# rs41.net
KiCad netlist of a schematic drawn in EAGLE
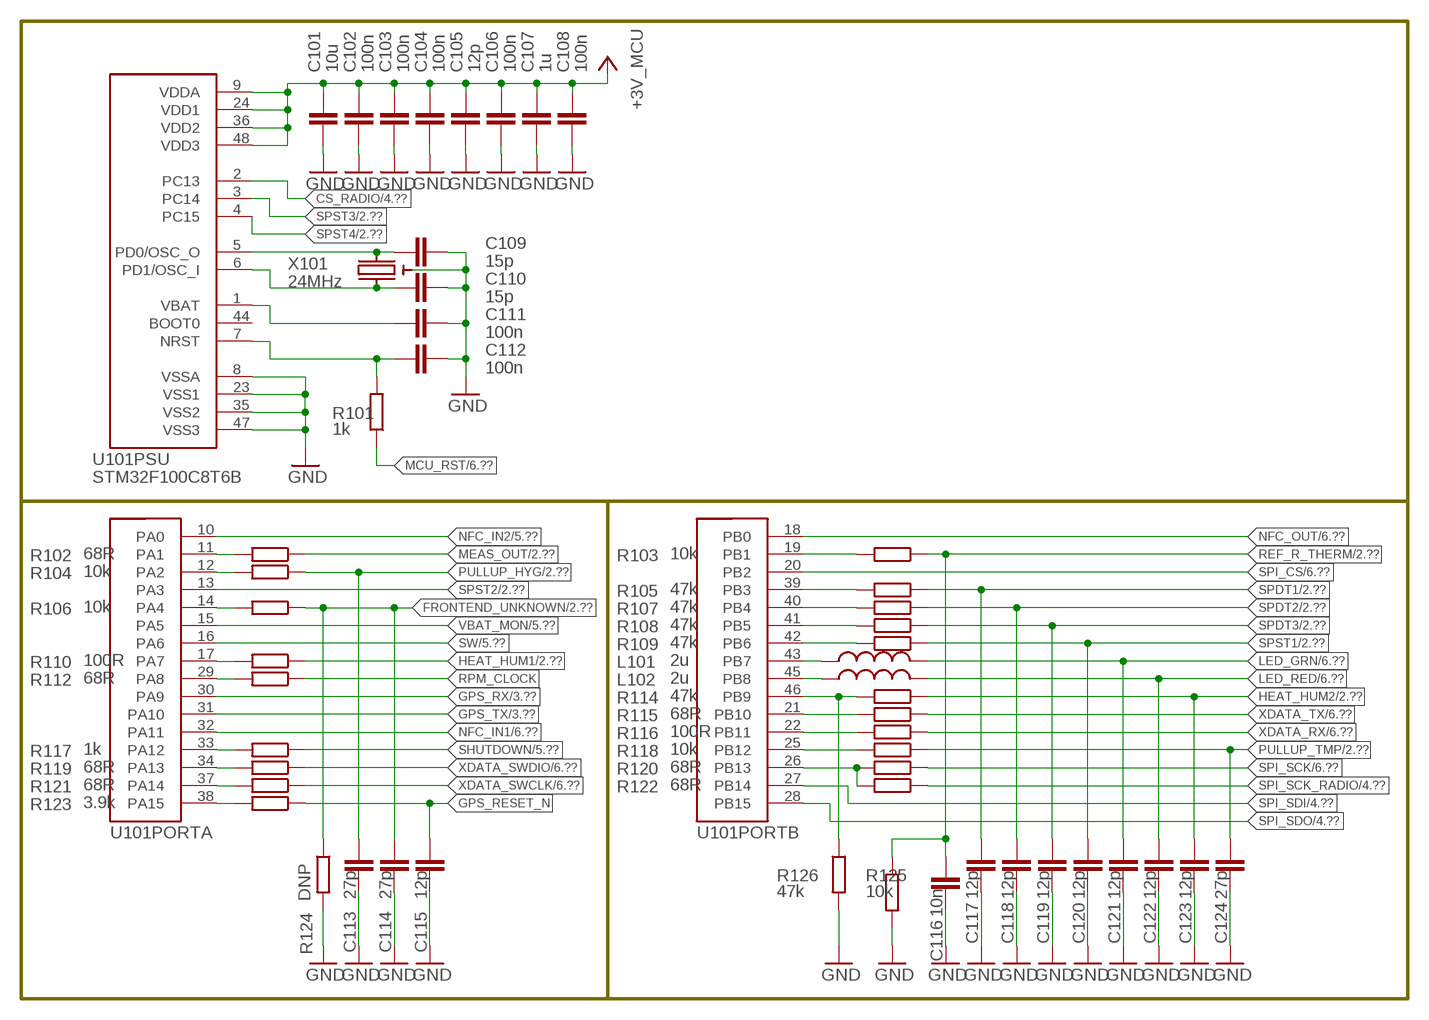
[diagram p0: schematic, sheet 1]
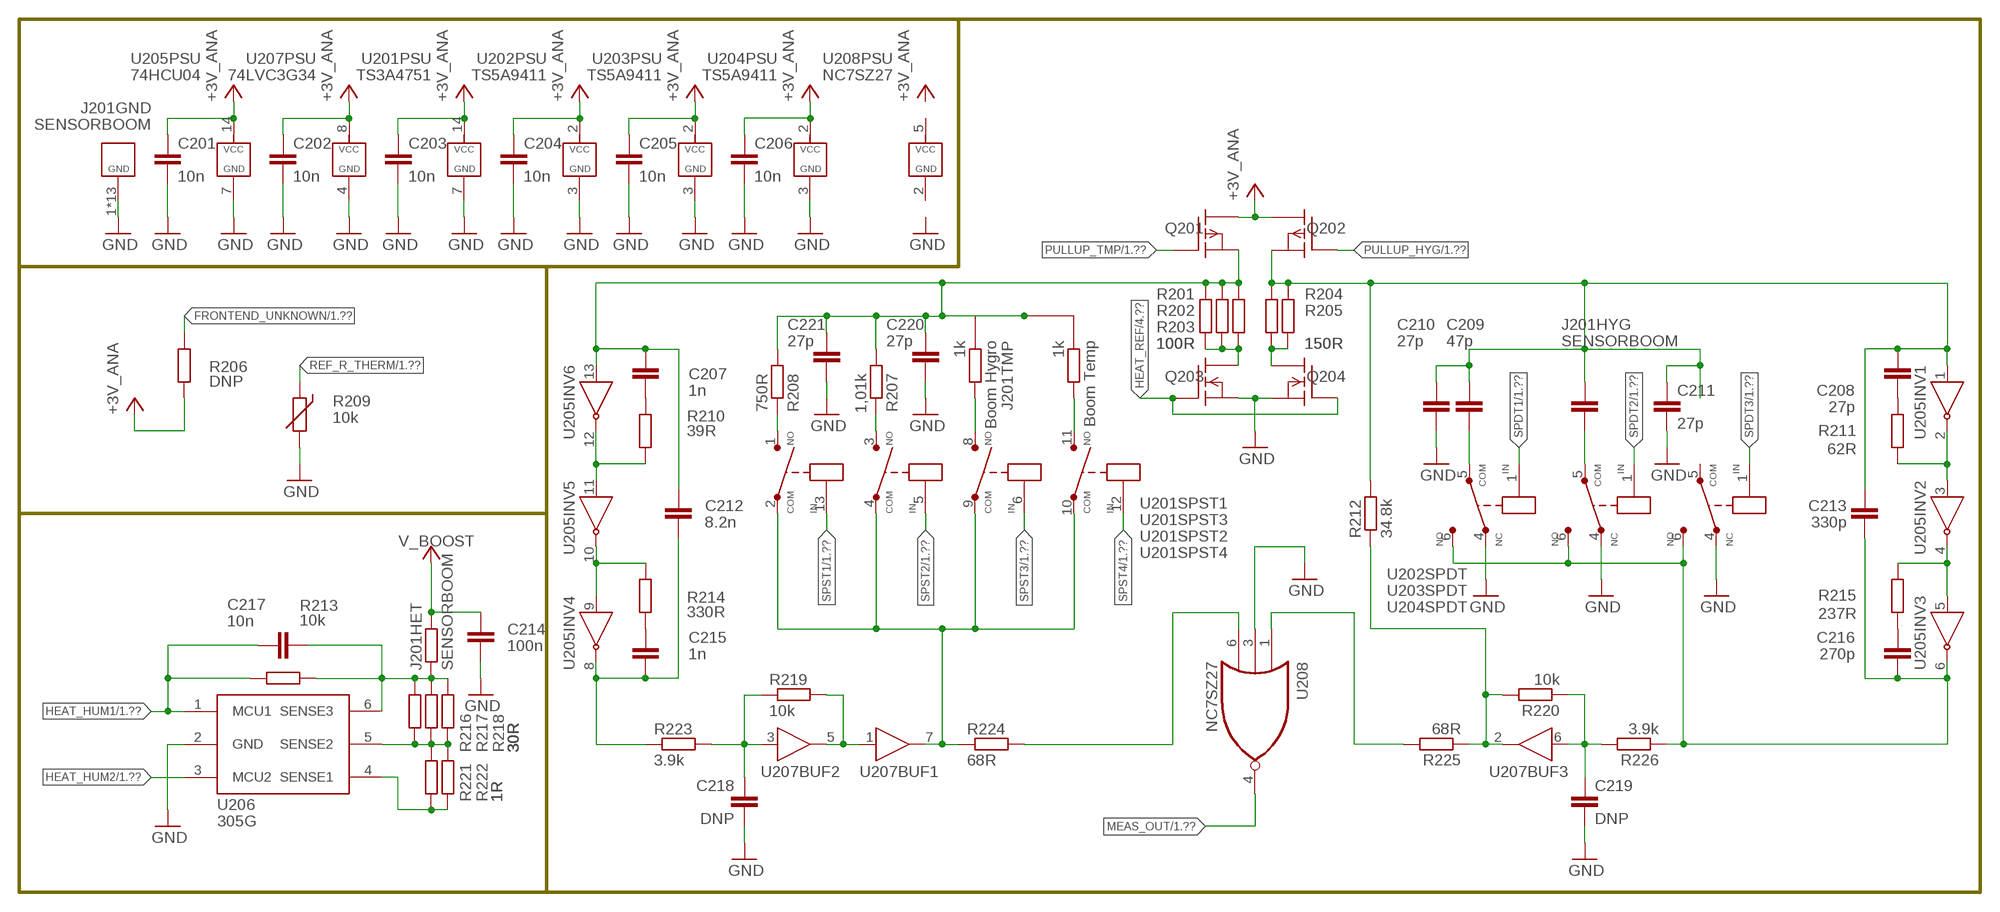
[diagram p1: schematic, sheet 2]
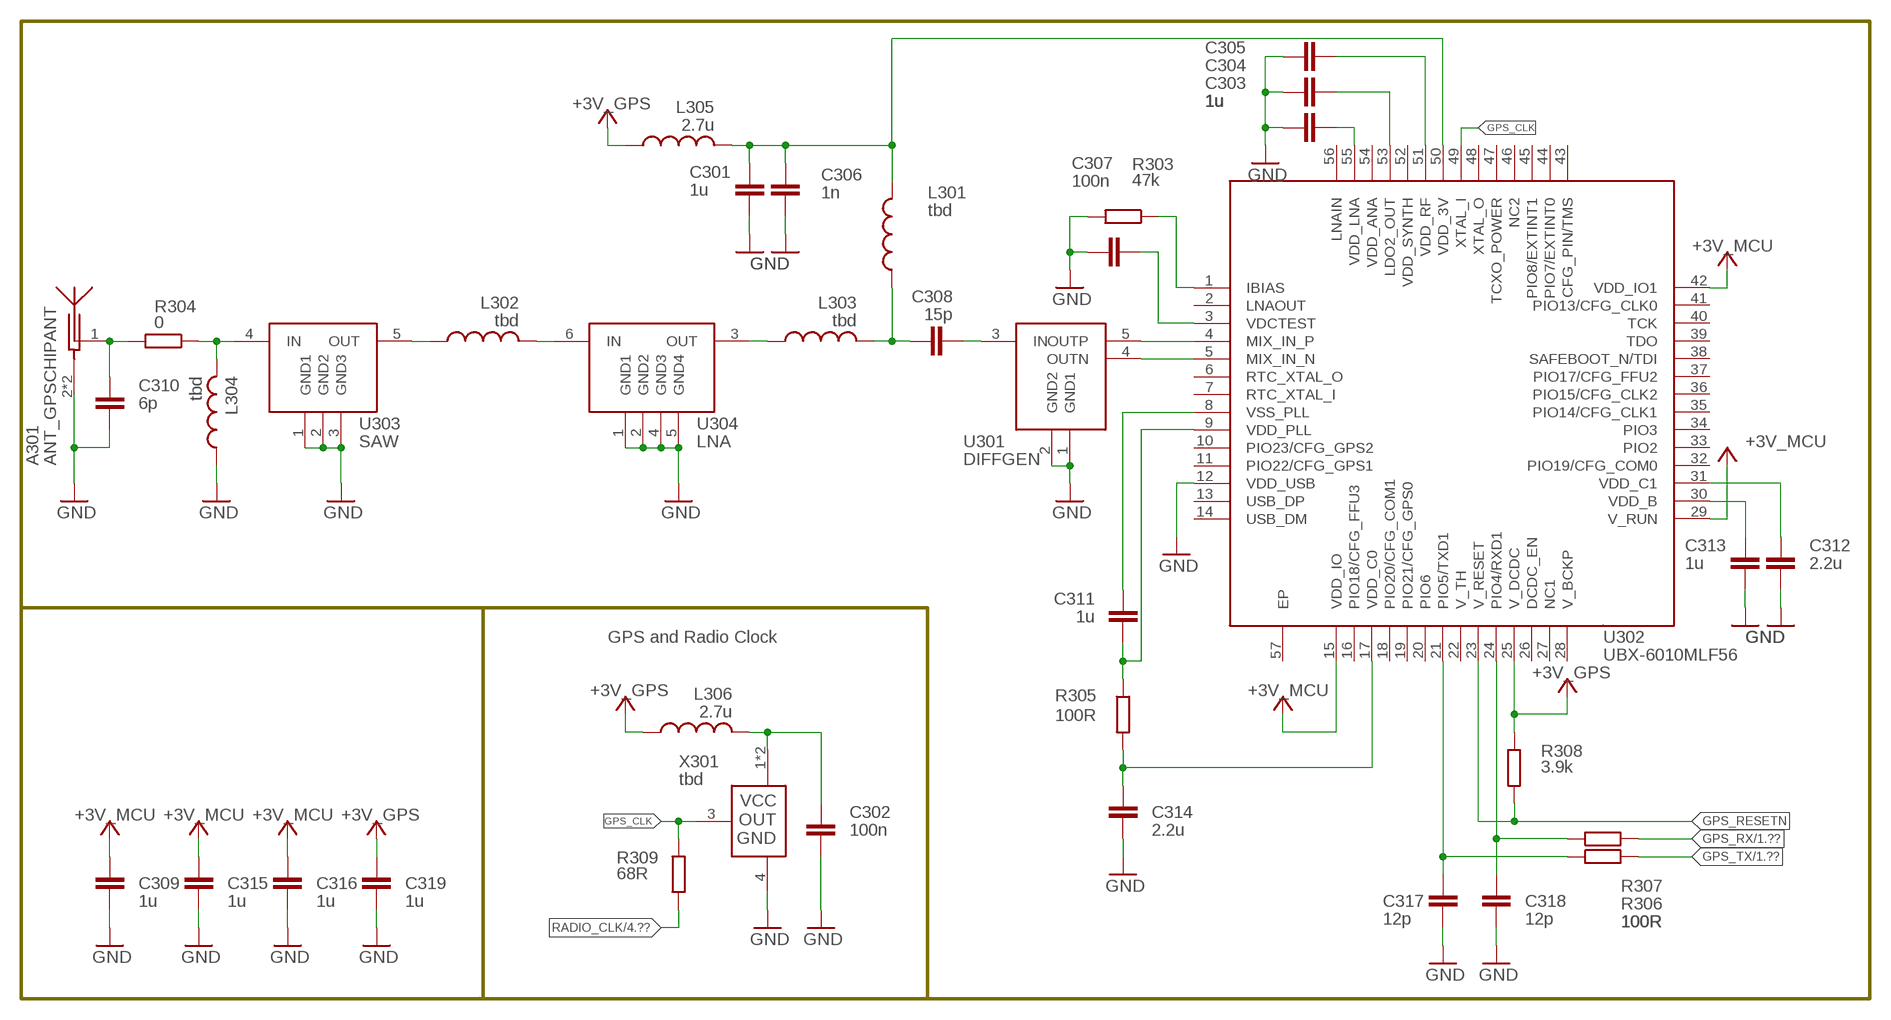
[diagram p2: schematic, sheet 3]
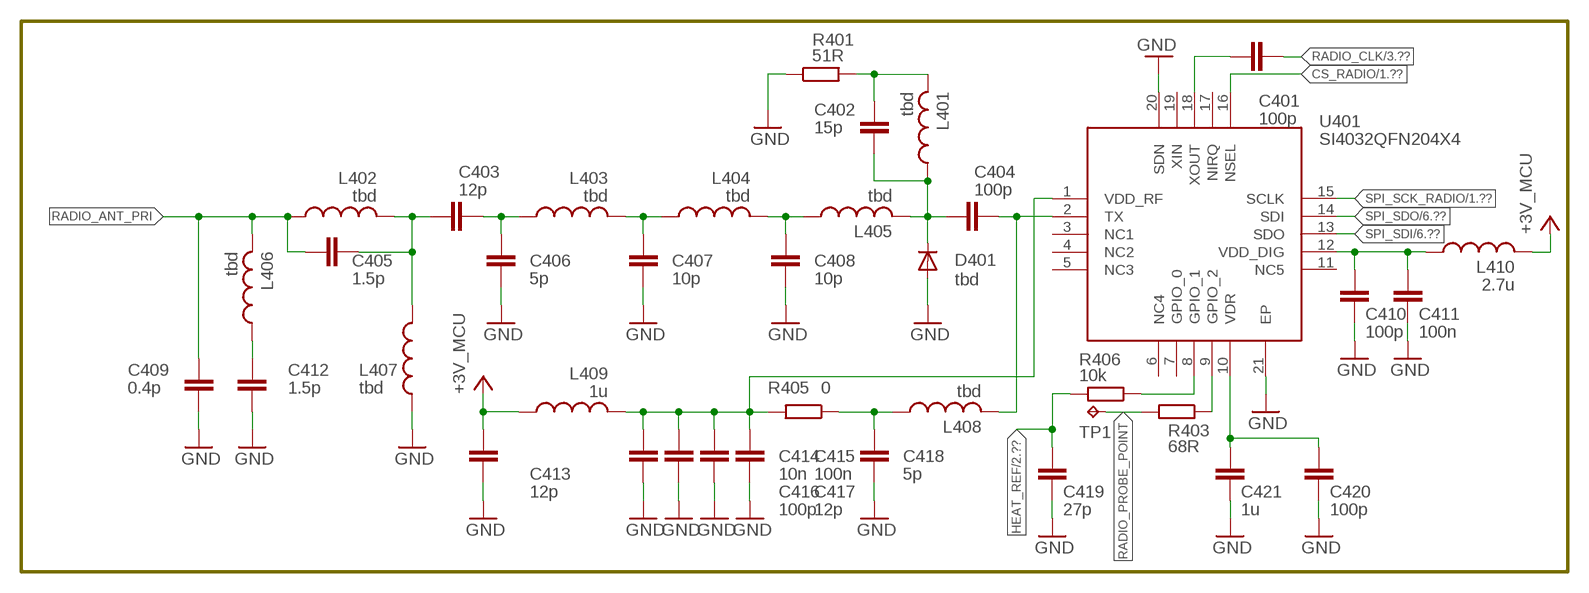
[diagram p3: schematic, sheet 4]
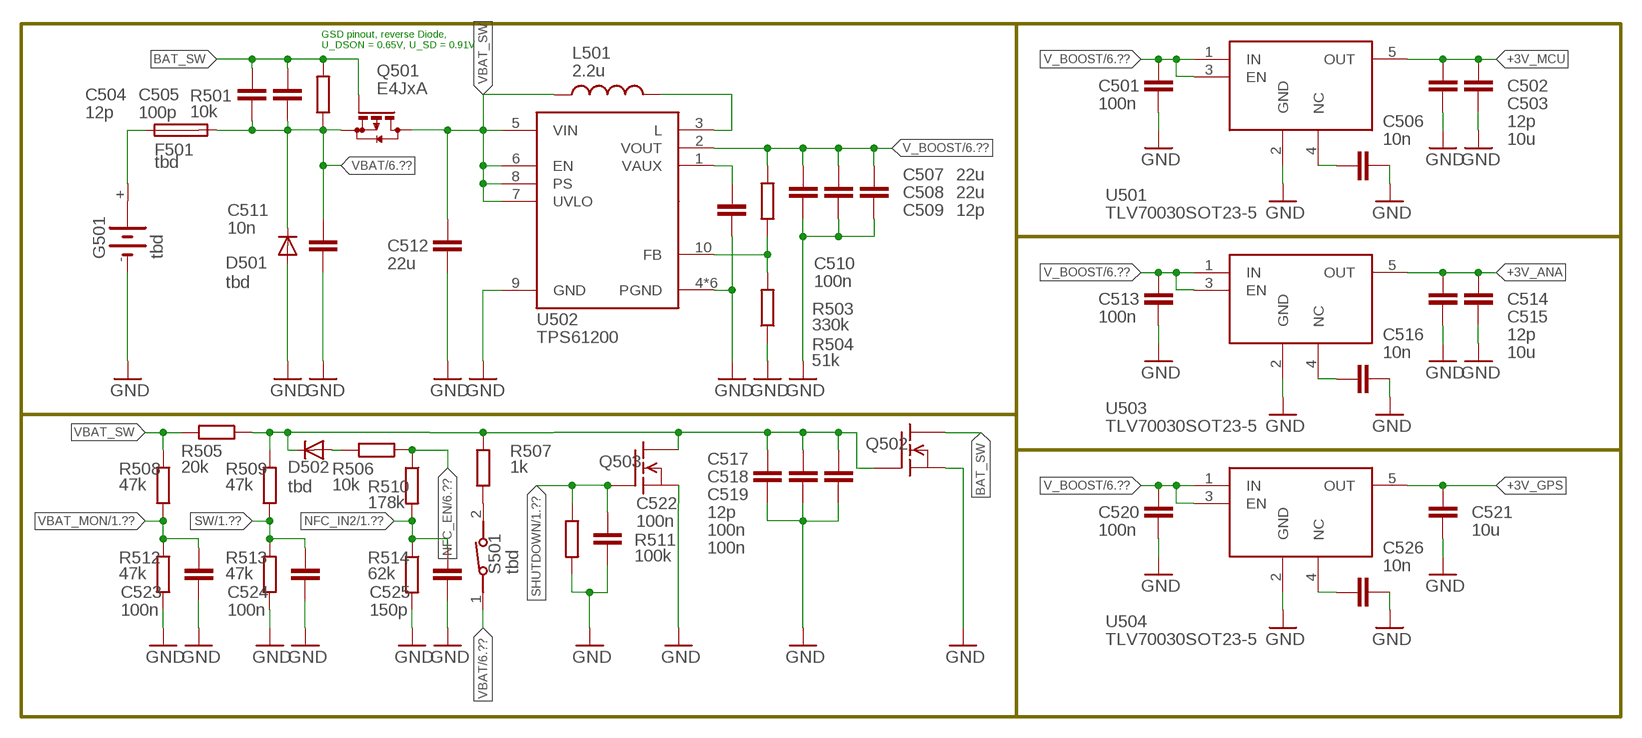
[diagram p4: schematic, sheet 5]
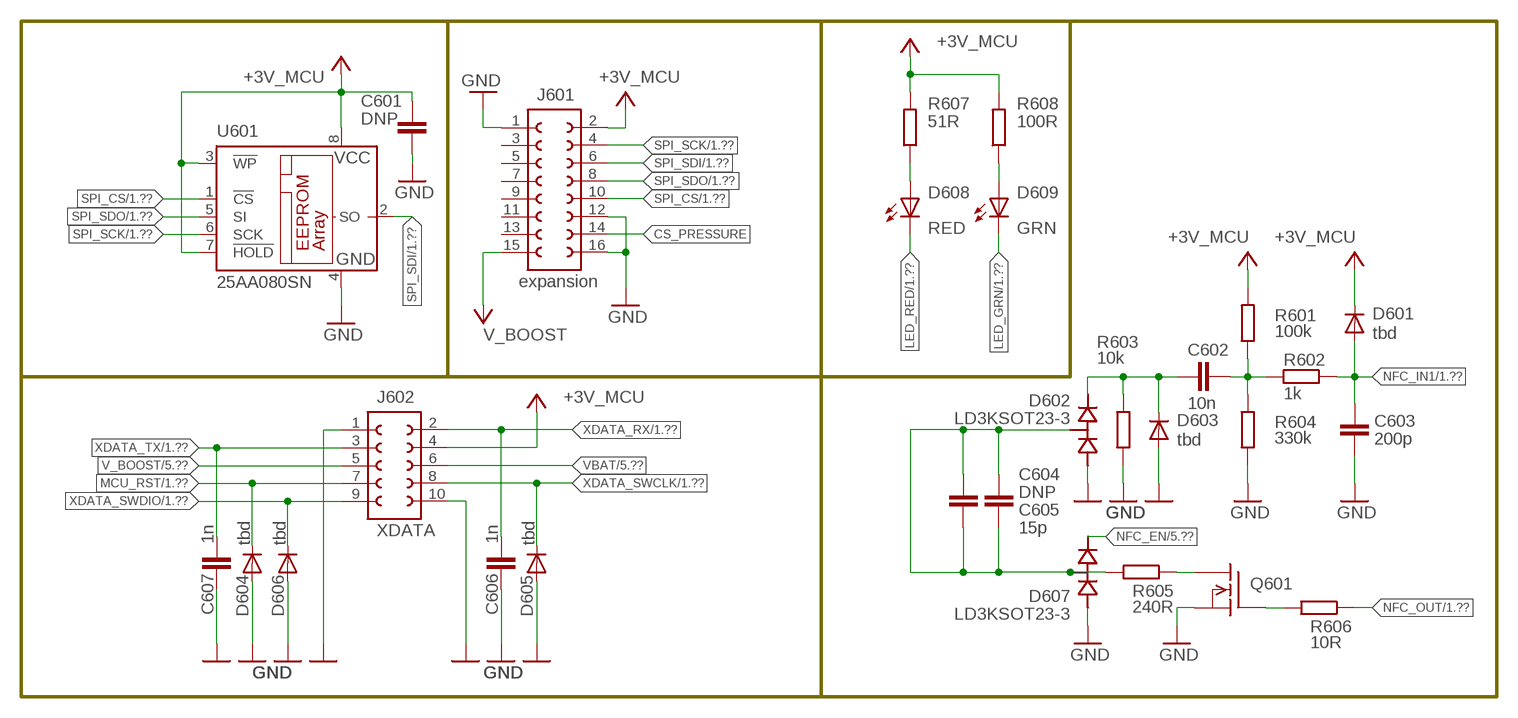
[diagram p5: schematic, sheet 6]

(export (version "E")
  (design (tool "Eeschema 10.0.6"))
  (components
    (comp (ref "C201")
      (value "10n")
      (footprint "eagle-import:C0402")
      (libsource (lib "eagle-import") (part "C-EUC0402"))
    )
    (comp (ref "C202")
      (value "10n")
      (footprint "eagle-import:C0402")
      (libsource (lib "eagle-import") (part "C-EUC0402"))
    )
    (comp (ref "C203")
      (value "10n")
      (footprint "eagle-import:C0402")
      (libsource (lib "eagle-import") (part "C-EUC0402"))
    )
    (comp (ref "C204")
      (value "10n")
      (footprint "eagle-import:C0402")
      (libsource (lib "eagle-import") (part "C-EUC0402"))
    )
    (comp (ref "C205")
      (value "10n")
      (footprint "eagle-import:C0402")
      (libsource (lib "eagle-import") (part "C-EUC0402"))
    )
    (comp (ref "C206")
      (value "10n")
      (footprint "eagle-import:C0402")
      (libsource (lib "eagle-import") (part "C-EUC0402"))
    )
    (comp (ref "C207")
      (value "1n")
      (footprint "eagle-import:C0402")
      (libsource (lib "eagle-import") (part "C-EUC0402"))
    )
    (comp (ref "C208")
      (value "27p")
      (footprint "eagle-import:C0402")
      (libsource (lib "eagle-import") (part "C-EUC0402"))
    )
    (comp (ref "C209")
      (value "47p")
      (footprint "eagle-import:C0603")
      (libsource (lib "eagle-import") (part "C-EUC0603"))
    )
    (comp (ref "C210")
      (value "27p")
      (footprint "eagle-import:C0402")
      (libsource (lib "eagle-import") (part "C-EUC0402"))
    )
    (comp (ref "C211")
      (value "27p")
      (footprint "eagle-import:C0402")
      (libsource (lib "eagle-import") (part "C-EUC0402"))
    )
    (comp (ref "C212")
      (value "8.2n")
      (footprint "eagle-import:C0603")
      (libsource (lib "eagle-import") (part "C-EUC0603"))
    )
    (comp (ref "C213")
      (value "330p")
      (footprint "eagle-import:C0402")
      (libsource (lib "eagle-import") (part "C-EUC0402"))
    )
    (comp (ref "C214")
      (value "100n")
      (footprint "eagle-import:C0402")
      (libsource (lib "eagle-import") (part "C-EUC0402"))
    )
    (comp (ref "C215")
      (value "1n")
      (footprint "eagle-import:C0402")
      (libsource (lib "eagle-import") (part "C-EUC0402"))
    )
    (comp (ref "C216")
      (value "270p")
      (footprint "eagle-import:C0402")
      (libsource (lib "eagle-import") (part "C-EUC0402"))
    )
    (comp (ref "C217")
      (value "10n")
      (footprint "eagle-import:C0402")
      (libsource (lib "eagle-import") (part "C-EUC0402"))
    )
    (comp (ref "C218")
      (value "DNP")
      (footprint "eagle-import:C0402")
      (libsource (lib "eagle-import") (part "C-EUC0402"))
    )
    (comp (ref "C219")
      (value "DNP")
      (footprint "eagle-import:C0402")
      (libsource (lib "eagle-import") (part "C-EUC0402"))
    )
    (comp (ref "C220")
      (value "27p")
      (footprint "eagle-import:C0402")
      (libsource (lib "eagle-import") (part "C-EUC0402"))
    )
    (comp (ref "C221")
      (value "27p")
      (footprint "eagle-import:C0402")
      (libsource (lib "eagle-import") (part "C-EUC0402"))
    )
    (comp (ref "J201")
      (value "SENSORBOOM")
      (footprint "eagle-import:687316124422")
      (libsource (lib "eagle-import") (part "SENSORBOOM"))
    )
    (comp (ref "Q201")
      (value "BSS92")
      (footprint "eagle-import:TO92")
      (libsource (lib "eagle-import") (part "BSS92"))
    )
    (comp (ref "Q202")
      (value "BSS92")
      (footprint "eagle-import:TO92")
      (libsource (lib "eagle-import") (part "BSS92"))
    )
    (comp (ref "Q203")
      (value "BSS101")
      (footprint "eagle-import:TO92")
      (libsource (lib "eagle-import") (part "BSS101"))
    )
    (comp (ref "Q204")
      (value "BSS101")
      (footprint "eagle-import:TO92")
      (libsource (lib "eagle-import") (part "BSS101"))
    )
    (comp (ref "R201")
      (value "100R")
      (footprint "eagle-import:R0603")
      (libsource (lib "eagle-import") (part "R-EU_R0603"))
    )
    (comp (ref "R202")
      (value "100R")
      (footprint "eagle-import:R0603")
      (libsource (lib "eagle-import") (part "R-EU_R0603"))
    )
    (comp (ref "R203")
      (value "100R")
      (footprint "eagle-import:R0603")
      (libsource (lib "eagle-import") (part "R-EU_R0603"))
    )
    (comp (ref "R204")
      (value "150R")
      (footprint "eagle-import:R0603")
      (libsource (lib "eagle-import") (part "R-EU_R0603"))
    )
    (comp (ref "R205")
      (value "150R")
      (footprint "eagle-import:R0603")
      (libsource (lib "eagle-import") (part "R-EU_R0603"))
    )
    (comp (ref "R206")
      (value "DNP")
      (footprint "eagle-import:R0402")
      (libsource (lib "eagle-import") (part "R-EU_R0402"))
    )
    (comp (ref "R207")
      (value "1,01k")
      (footprint "eagle-import:R0805")
      (libsource (lib "eagle-import") (part "R-EU_R0805"))
    )
    (comp (ref "R208")
      (value "750R")
      (footprint "eagle-import:R0805")
      (libsource (lib "eagle-import") (part "R-EU_R0805"))
    )
    (comp (ref "R209")
      (value "10k")
      (footprint "eagle-import:0402")
      (libsource (lib "eagle-import") (part "THERMISTOR0402"))
    )
    (comp (ref "R210")
      (value "39R")
      (footprint "eagle-import:R0402")
      (libsource (lib "eagle-import") (part "R-EU_R0402"))
    )
    (comp (ref "R211")
      (value "62R")
      (footprint "eagle-import:R0402")
      (libsource (lib "eagle-import") (part "R-EU_R0402"))
    )
    (comp (ref "R212")
      (value "34.8k")
      (footprint "eagle-import:R0402")
      (libsource (lib "eagle-import") (part "R-EU_R0402"))
    )
    (comp (ref "R213")
      (value "10k")
      (footprint "eagle-import:R0402")
      (libsource (lib "eagle-import") (part "R-EU_R0402"))
    )
    (comp (ref "R214")
      (value "330R")
      (footprint "eagle-import:R0402")
      (libsource (lib "eagle-import") (part "R-EU_R0402"))
    )
    (comp (ref "R215")
      (value "237R")
      (footprint "eagle-import:R0402")
      (libsource (lib "eagle-import") (part "R-EU_R0402"))
    )
    (comp (ref "R216")
      (value "30R")
      (footprint "eagle-import:R0603")
      (libsource (lib "eagle-import") (part "R-EU_R0603"))
    )
    (comp (ref "R217")
      (value "30R")
      (footprint "eagle-import:R0603")
      (libsource (lib "eagle-import") (part "R-EU_R0603"))
    )
    (comp (ref "R218")
      (value "30R")
      (footprint "eagle-import:R0603")
      (libsource (lib "eagle-import") (part "R-EU_R0603"))
    )
    (comp (ref "R219")
      (value "10k")
      (footprint "eagle-import:R0402")
      (libsource (lib "eagle-import") (part "R-EU_R0402"))
    )
    (comp (ref "R220")
      (value "10k")
      (footprint "eagle-import:R0402")
      (libsource (lib "eagle-import") (part "R-EU_R0402"))
    )
    (comp (ref "R221")
      (value "1R")
      (footprint "eagle-import:R0402")
      (libsource (lib "eagle-import") (part "R-EU_R0402"))
    )
    (comp (ref "R222")
      (value "1R")
      (footprint "eagle-import:R0402")
      (libsource (lib "eagle-import") (part "R-EU_R0402"))
    )
    (comp (ref "R223")
      (value "3.9k")
      (footprint "eagle-import:R0402")
      (libsource (lib "eagle-import") (part "R-EU_R0402"))
    )
    (comp (ref "R224")
      (value "68R")
      (footprint "eagle-import:R0402")
      (libsource (lib "eagle-import") (part "R-EU_R0402"))
    )
    (comp (ref "R225")
      (value "68R")
      (footprint "eagle-import:R0402")
      (libsource (lib "eagle-import") (part "R-EU_R0402"))
    )
    (comp (ref "R226")
      (value "3.9k")
      (footprint "eagle-import:R0402")
      (libsource (lib "eagle-import") (part "R-EU_R0402"))
    )
    (comp (ref "U201")
      (value "TS3A4751")
      (footprint "eagle-import:TSSOP14")
      (libsource (lib "eagle-import") (part "TS3A4751"))
    )
    (comp (ref "U202")
      (value "TS5A9411")
      (footprint "eagle-import:SOT23-6")
      (libsource (lib "eagle-import") (part "TS5A9411"))
    )
    (comp (ref "U203")
      (value "TS5A9411")
      (footprint "eagle-import:SOT23-6")
      (libsource (lib "eagle-import") (part "TS5A9411"))
    )
    (comp (ref "U204")
      (value "TS5A9411")
      (footprint "eagle-import:SOT23-6")
      (libsource (lib "eagle-import") (part "TS5A9411"))
    )
    (comp (ref "U205")
      (value "74HCU04")
      (footprint "eagle-import:TSSOP14")
      (libsource (lib "eagle-import") (part "74HCU04"))
    )
    (comp (ref "U206")
      (value "305G")
      (footprint "eagle-import:SOT23-6")
      (libsource (lib "eagle-import") (part "305G"))
    )
    (comp (ref "U207")
      (value "74LVC3G34")
      (footprint "eagle-import:GHI-IC_VSSOP8(TI)")
      (libsource (lib "eagle-import") (part "74LVC3G34"))
    )
    (comp (ref "U208")
      (value "NC7SZ27")
      (footprint "eagle-import:SOT23-6")
      (libsource (lib "eagle-import") (part "NC7SZ27"))
    )
    (comp (ref "C101")
      (value "10u")
      (footprint "eagle-import:C0603")
      (libsource (lib "eagle-import") (part "C-EUC0603"))
    )
    (comp (ref "C102")
      (value "100n")
      (footprint "eagle-import:C0402")
      (libsource (lib "eagle-import") (part "C-EUC0402"))
    )
    (comp (ref "C103")
      (value "100n")
      (footprint "eagle-import:C0402")
      (libsource (lib "eagle-import") (part "C-EUC0402"))
    )
    (comp (ref "C104")
      (value "100n")
      (footprint "eagle-import:C0402")
      (libsource (lib "eagle-import") (part "C-EUC0402"))
    )
    (comp (ref "C105")
      (value "12p")
      (footprint "eagle-import:C0402")
      (libsource (lib "eagle-import") (part "C-EUC0402"))
    )
    (comp (ref "C106")
      (value "100n")
      (footprint "eagle-import:C0402")
      (libsource (lib "eagle-import") (part "C-EUC0402"))
    )
    (comp (ref "C107")
      (value "1u")
      (footprint "eagle-import:C0402")
      (libsource (lib "eagle-import") (part "C-EUC0402"))
    )
    (comp (ref "C108")
      (value "100n")
      (footprint "eagle-import:C0402")
      (libsource (lib "eagle-import") (part "C-EUC0402"))
    )
    (comp (ref "C109")
      (value "15p")
      (footprint "eagle-import:C0402")
      (libsource (lib "eagle-import") (part "C-EUC0402"))
    )
    (comp (ref "C110")
      (value "15p")
      (footprint "eagle-import:C0402")
      (libsource (lib "eagle-import") (part "C-EUC0402"))
    )
    (comp (ref "C111")
      (value "100n")
      (footprint "eagle-import:C0402")
      (libsource (lib "eagle-import") (part "C-EUC0402"))
    )
    (comp (ref "C112")
      (value "100n")
      (footprint "eagle-import:C0402")
      (libsource (lib "eagle-import") (part "C-EUC0402"))
    )
    (comp (ref "C113")
      (value "27p")
      (footprint "eagle-import:C0402")
      (libsource (lib "eagle-import") (part "C-EUC0402"))
    )
    (comp (ref "C114")
      (value "27p")
      (footprint "eagle-import:C0402")
      (libsource (lib "eagle-import") (part "C-EUC0402"))
    )
    (comp (ref "C115")
      (value "12p")
      (footprint "eagle-import:C0402")
      (libsource (lib "eagle-import") (part "C-EUC0402"))
    )
    (comp (ref "C116")
      (value "10n")
      (footprint "eagle-import:C0402")
      (libsource (lib "eagle-import") (part "C-EUC0402"))
    )
    (comp (ref "C117")
      (value "12p")
      (footprint "eagle-import:C0402")
      (libsource (lib "eagle-import") (part "C-EUC0402"))
    )
    (comp (ref "C118")
      (value "12p")
      (footprint "eagle-import:C0402")
      (libsource (lib "eagle-import") (part "C-EUC0402"))
    )
    (comp (ref "C119")
      (value "12p")
      (footprint "eagle-import:C0402")
      (libsource (lib "eagle-import") (part "C-EUC0402"))
    )
    (comp (ref "C120")
      (value "12p")
      (footprint "eagle-import:C0402")
      (libsource (lib "eagle-import") (part "C-EUC0402"))
    )
    (comp (ref "C121")
      (value "12p")
      (footprint "eagle-import:C0402")
      (libsource (lib "eagle-import") (part "C-EUC0402"))
    )
    (comp (ref "C122")
      (value "12p")
      (footprint "eagle-import:C0402")
      (libsource (lib "eagle-import") (part "C-EUC0402"))
    )
    (comp (ref "C123")
      (value "12p")
      (footprint "eagle-import:C0402")
      (libsource (lib "eagle-import") (part "C-EUC0402"))
    )
    (comp (ref "C124")
      (value "27p")
      (footprint "eagle-import:C0402")
      (libsource (lib "eagle-import") (part "C-EUC0402"))
    )
    (comp (ref "L101")
      (value "2u")
      (footprint "eagle-import:0402")
      (libsource (lib "eagle-import") (part "L0402"))
    )
    (comp (ref "L102")
      (value "2u")
      (footprint "eagle-import:0402")
      (libsource (lib "eagle-import") (part "L0402"))
    )
    (comp (ref "R101")
      (value "1k")
      (footprint "eagle-import:R0402")
      (libsource (lib "eagle-import") (part "R-EU_R0402"))
    )
    (comp (ref "R102")
      (value "68R")
      (footprint "eagle-import:R0402")
      (libsource (lib "eagle-import") (part "R-EU_R0402"))
    )
    (comp (ref "R103")
      (value "10k")
      (footprint "eagle-import:R0402")
      (libsource (lib "eagle-import") (part "R-EU_R0402"))
    )
    (comp (ref "R104")
      (value "10k")
      (footprint "eagle-import:R0402")
      (libsource (lib "eagle-import") (part "R-EU_R0402"))
    )
    (comp (ref "R105")
      (value "47k")
      (footprint "eagle-import:R0402")
      (libsource (lib "eagle-import") (part "R-EU_R0402"))
    )
    (comp (ref "R106")
      (value "10k")
      (footprint "eagle-import:R0402")
      (libsource (lib "eagle-import") (part "R-EU_R0402"))
    )
    (comp (ref "R107")
      (value "47k")
      (footprint "eagle-import:R0402")
      (libsource (lib "eagle-import") (part "R-EU_R0402"))
    )
    (comp (ref "R108")
      (value "47k")
      (footprint "eagle-import:R0402")
      (libsource (lib "eagle-import") (part "R-EU_R0402"))
    )
    (comp (ref "R109")
      (value "47k")
      (footprint "eagle-import:R0402")
      (libsource (lib "eagle-import") (part "R-EU_R0402"))
    )
    (comp (ref "R110")
      (value "100R")
      (footprint "eagle-import:R0402")
      (libsource (lib "eagle-import") (part "R-EU_R0402"))
    )
    (comp (ref "R112")
      (value "68R")
      (footprint "eagle-import:R0402")
      (libsource (lib "eagle-import") (part "R-EU_R0402"))
    )
    (comp (ref "R114")
      (value "47k")
      (footprint "eagle-import:R0402")
      (libsource (lib "eagle-import") (part "R-EU_R0402"))
    )
    (comp (ref "R115")
      (value "68R")
      (footprint "eagle-import:R0402")
      (libsource (lib "eagle-import") (part "R-EU_R0402"))
    )
    (comp (ref "R116")
      (value "100R")
      (footprint "eagle-import:R0402")
      (libsource (lib "eagle-import") (part "R-EU_R0402"))
    )
    (comp (ref "R117")
      (value "1k")
      (footprint "eagle-import:R0402")
      (libsource (lib "eagle-import") (part "R-EU_R0402"))
    )
    (comp (ref "R118")
      (value "10k")
      (footprint "eagle-import:R0402")
      (libsource (lib "eagle-import") (part "R-EU_R0402"))
    )
    (comp (ref "R119")
      (value "68R")
      (footprint "eagle-import:R0402")
      (libsource (lib "eagle-import") (part "R-EU_R0402"))
    )
    (comp (ref "R120")
      (value "68R")
      (footprint "eagle-import:R0402")
      (libsource (lib "eagle-import") (part "R-EU_R0402"))
    )
    (comp (ref "R121")
      (value "68R")
      (footprint "eagle-import:R0402")
      (libsource (lib "eagle-import") (part "R-EU_R0402"))
    )
    (comp (ref "R122")
      (value "68R")
      (footprint "eagle-import:R0402")
      (libsource (lib "eagle-import") (part "R-EU_R0402"))
    )
    (comp (ref "R123")
      (value "3.9k")
      (footprint "eagle-import:R0402")
      (libsource (lib "eagle-import") (part "R-EU_R0402"))
    )
    (comp (ref "R124")
      (value "DNP")
      (footprint "eagle-import:R0402")
      (libsource (lib "eagle-import") (part "R-EU_R0402"))
    )
    (comp (ref "R125")
      (value "10k")
      (footprint "eagle-import:R0402")
      (libsource (lib "eagle-import") (part "R-EU_R0402"))
    )
    (comp (ref "R126")
      (value "47k")
      (footprint "eagle-import:R0402")
      (libsource (lib "eagle-import") (part "R-EU_R0402"))
    )
    (comp (ref "U101")
      (value "STM32F100C8T6B")
      (footprint "eagle-import:LQFP48")
      (libsource (lib "eagle-import") (part "STM32F100C8LQFP48"))
    )
    (comp (ref "X101")
      (value "24MHz")
      (footprint "eagle-import:OSCCC650X400X120")
      (libsource (lib "eagle-import") (part "OSC_MCU"))
    )
    (comp (ref "C601")
      (value "DNP")
      (footprint "eagle-import:C0402")
      (libsource (lib "eagle-import") (part "C-EUC0402"))
    )
    (comp (ref "C602")
      (value "10n")
      (footprint "eagle-import:C0402")
      (libsource (lib "eagle-import") (part "C-EUC0402"))
    )
    (comp (ref "C603")
      (value "200p")
      (footprint "eagle-import:C0402")
      (libsource (lib "eagle-import") (part "C-EUC0402"))
    )
    (comp (ref "C604")
      (value "DNP")
      (footprint "eagle-import:C0402")
      (libsource (lib "eagle-import") (part "C-EUC0402"))
    )
    (comp (ref "C605")
      (value "15p")
      (footprint "eagle-import:C0402")
      (libsource (lib "eagle-import") (part "C-EUC0402"))
    )
    (comp (ref "C606")
      (value "1n")
      (footprint "eagle-import:C0402")
      (libsource (lib "eagle-import") (part "C-EUC0402"))
    )
    (comp (ref "C607")
      (value "1n")
      (footprint "eagle-import:C0402")
      (libsource (lib "eagle-import") (part "C-EUC0402"))
    )
    (comp (ref "D601")
      (value "tbd")
      (footprint "eagle-import:DO41-10")
      (libsource (lib "eagle-import") (part "1N4004"))
    )
    (comp (ref "D602")
      (value "LD3KSOT23-3")
      (footprint "eagle-import:SOT23-3")
      (libsource (lib "eagle-import") (part "LD3KSOT23-3"))
    )
    (comp (ref "D603")
      (value "tbd")
      (footprint "eagle-import:DO41-10")
      (libsource (lib "eagle-import") (part "1N4004"))
    )
    (comp (ref "D604")
      (value "tbd")
      (footprint "eagle-import:DO41-10")
      (libsource (lib "eagle-import") (part "1N4004"))
    )
    (comp (ref "D605")
      (value "tbd")
      (footprint "eagle-import:DO41-10")
      (libsource (lib "eagle-import") (part "1N4004"))
    )
    (comp (ref "D606")
      (value "tbd")
      (footprint "eagle-import:DO41-10")
      (libsource (lib "eagle-import") (part "1N4004"))
    )
    (comp (ref "D607")
      (value "LD3KSOT23-3")
      (footprint "eagle-import:SOT23-3")
      (libsource (lib "eagle-import") (part "LD3KSOT23-3"))
    )
    (comp (ref "D608")
      (value "RED")
      (footprint "eagle-import:CHIPLED_0603")
      (libsource (lib "eagle-import") (part "LEDCHIPLED_0603"))
    )
    (comp (ref "D609")
      (value "GRN")
      (footprint "eagle-import:CHIPLED_0603")
      (libsource (lib "eagle-import") (part "LEDCHIPLED_0603"))
    )
    (comp (ref "J601")
      (value "expansion")
      (footprint "eagle-import:62001621121")
      (libsource (lib "eagle-import") (part "62001621121"))
    )
    (comp (ref "J602")
      (value "XDATA")
      (footprint "eagle-import:62001021121")
      (libsource (lib "eagle-import") (part "62001021121"))
    )
    (comp (ref "Q601")
      (value "BSS101")
      (footprint "eagle-import:TO92")
      (libsource (lib "eagle-import") (part "BSS101"))
    )
    (comp (ref "R601")
      (value "100k")
      (footprint "eagle-import:R0402")
      (libsource (lib "eagle-import") (part "R-EU_R0402"))
    )
    (comp (ref "R602")
      (value "1k")
      (footprint "eagle-import:R0402")
      (libsource (lib "eagle-import") (part "R-EU_R0402"))
    )
    (comp (ref "R603")
      (value "10k")
      (footprint "eagle-import:R0402")
      (libsource (lib "eagle-import") (part "R-EU_R0402"))
    )
    (comp (ref "R604")
      (value "330k")
      (footprint "eagle-import:R0402")
      (libsource (lib "eagle-import") (part "R-EU_R0402"))
    )
    (comp (ref "R605")
      (value "240R")
      (footprint "eagle-import:R0402")
      (libsource (lib "eagle-import") (part "R-EU_R0402"))
    )
    (comp (ref "R606")
      (value "10R")
      (footprint "eagle-import:R0402")
      (libsource (lib "eagle-import") (part "R-EU_R0402"))
    )
    (comp (ref "R607")
      (value "51R")
      (footprint "eagle-import:R0402")
      (libsource (lib "eagle-import") (part "R-EU_R0402"))
    )
    (comp (ref "R608")
      (value "100R")
      (footprint "eagle-import:R0402")
      (libsource (lib "eagle-import") (part "R-EU_R0402"))
    )
    (comp (ref "U601")
      (value "25AA080SN")
      (footprint "eagle-import:SO-08")
      (fields (field (name "MF") "MICROCHIP") (field (name "MPN") "25AA080/SN"))
      (libsource (lib "eagle-import") (part "25SNAA080"))
    )
    (comp (ref "C501")
      (value "100n")
      (footprint "eagle-import:C0402")
      (libsource (lib "eagle-import") (part "C-EUC0402"))
    )
    (comp (ref "C502")
      (value "12p")
      (footprint "eagle-import:C0402")
      (libsource (lib "eagle-import") (part "C-EUC0402"))
    )
    (comp (ref "C503")
      (value "10u")
      (footprint "eagle-import:C0603")
      (libsource (lib "eagle-import") (part "C-EUC0603"))
    )
    (comp (ref "C504")
      (value "12p")
      (footprint "eagle-import:C0402")
      (libsource (lib "eagle-import") (part "C-EUC0402"))
    )
    (comp (ref "C505")
      (value "100p")
      (footprint "eagle-import:C0402")
      (libsource (lib "eagle-import") (part "C-EUC0402"))
    )
    (comp (ref "C506")
      (value "10n")
      (footprint "eagle-import:C0402")
      (libsource (lib "eagle-import") (part "C-EUC0402"))
    )
    (comp (ref "C507")
      (value "22u")
      (footprint "eagle-import:C0805")
      (libsource (lib "eagle-import") (part "C-EUC0805"))
    )
    (comp (ref "C508")
      (value "22u")
      (footprint "eagle-import:C0805")
      (libsource (lib "eagle-import") (part "C-EUC0805"))
    )
    (comp (ref "C509")
      (value "12p")
      (footprint "eagle-import:C0402")
      (libsource (lib "eagle-import") (part "C-EUC0402"))
    )
    (comp (ref "C510")
      (value "100n")
      (footprint "eagle-import:C0402")
      (libsource (lib "eagle-import") (part "C-EUC0402"))
    )
    (comp (ref "C511")
      (value "10n")
      (footprint "eagle-import:C0402")
      (libsource (lib "eagle-import") (part "C-EUC0402"))
    )
    (comp (ref "C512")
      (value "22u")
      (footprint "eagle-import:C0805")
      (libsource (lib "eagle-import") (part "C-EUC0805"))
    )
    (comp (ref "C513")
      (value "100n")
      (footprint "eagle-import:C0402")
      (libsource (lib "eagle-import") (part "C-EUC0402"))
    )
    (comp (ref "C514")
      (value "12p")
      (footprint "eagle-import:C0402")
      (libsource (lib "eagle-import") (part "C-EUC0402"))
    )
    (comp (ref "C515")
      (value "10u")
      (footprint "eagle-import:C0603")
      (libsource (lib "eagle-import") (part "C-EUC0603"))
    )
    (comp (ref "C516")
      (value "10n")
      (footprint "eagle-import:C0402")
      (libsource (lib "eagle-import") (part "C-EUC0402"))
    )
    (comp (ref "C517")
      (value "12p")
      (footprint "eagle-import:C0402")
      (libsource (lib "eagle-import") (part "C-EUC0402"))
    )
    (comp (ref "C518")
      (value "100n")
      (footprint "eagle-import:C0402")
      (libsource (lib "eagle-import") (part "C-EUC0402"))
    )
    (comp (ref "C519")
      (value "100n")
      (footprint "eagle-import:C0402")
      (libsource (lib "eagle-import") (part "C-EUC0402"))
    )
    (comp (ref "C520")
      (value "100n")
      (footprint "eagle-import:C0402")
      (libsource (lib "eagle-import") (part "C-EUC0402"))
    )
    (comp (ref "C521")
      (value "10u")
      (footprint "eagle-import:C0603")
      (libsource (lib "eagle-import") (part "C-EUC0603"))
    )
    (comp (ref "C522")
      (value "100n")
      (footprint "eagle-import:C0402")
      (libsource (lib "eagle-import") (part "C-EUC0402"))
    )
    (comp (ref "C523")
      (value "100n")
      (footprint "eagle-import:C0402")
      (libsource (lib "eagle-import") (part "C-EUC0402"))
    )
    (comp (ref "C524")
      (value "100n")
      (footprint "eagle-import:C0402")
      (libsource (lib "eagle-import") (part "C-EUC0402"))
    )
    (comp (ref "C525")
      (value "150p")
      (footprint "eagle-import:C0402")
      (libsource (lib "eagle-import") (part "C-EUC0402"))
    )
    (comp (ref "C526")
      (value "10n")
      (footprint "eagle-import:C0402")
      (libsource (lib "eagle-import") (part "C-EUC0402"))
    )
    (comp (ref "D501")
      (value "tbd")
      (footprint "eagle-import:DO41-10")
      (libsource (lib "eagle-import") (part "1N4004"))
    )
    (comp (ref "D502")
      (value "tbd")
      (footprint "eagle-import:DO41-10")
      (libsource (lib "eagle-import") (part "1N4004"))
    )
    (comp (ref "F501")
      (value "tbd")
      (footprint "eagle-import:R0805")
      (libsource (lib "eagle-import") (part "FUSE"))
    )
    (comp (ref "G501")
      (value "tbd")
      (footprint "eagle-import:2V60R")
      (libsource (lib "eagle-import") (part "2V60R"))
    )
    (comp (ref "L501")
      (value "2.2u")
      (footprint "eagle-import:L_WE3816")
      (libsource (lib "eagle-import") (part "LWE3816"))
    )
    (comp (ref "Q501")
      (value "E4JxA")
      (footprint "eagle-import:SOT23")
      (libsource (lib "eagle-import") (part "BSS84"))
    )
    (comp (ref "Q502")
      (value "BSS101")
      (footprint "eagle-import:TO92")
      (libsource (lib "eagle-import") (part "BSS101"))
    )
    (comp (ref "Q503")
      (value "BSS101")
      (footprint "eagle-import:TO92")
      (libsource (lib "eagle-import") (part "BSS101"))
    )
    (comp (ref "R501")
      (value "10k")
      (footprint "eagle-import:R0402")
      (libsource (lib "eagle-import") (part "R-EU_R0402"))
    )
    (comp (ref "R503")
      (value "330k")
      (footprint "eagle-import:R0402")
      (libsource (lib "eagle-import") (part "R-EU_R0402"))
    )
    (comp (ref "R504")
      (value "51k")
      (footprint "eagle-import:R0402")
      (libsource (lib "eagle-import") (part "R-EU_R0402"))
    )
    (comp (ref "R505")
      (value "20k")
      (footprint "eagle-import:R0402")
      (libsource (lib "eagle-import") (part "R-EU_R0402"))
    )
    (comp (ref "R506")
      (value "10k")
      (footprint "eagle-import:R0402")
      (libsource (lib "eagle-import") (part "R-EU_R0402"))
    )
    (comp (ref "R507")
      (value "1k")
      (footprint "eagle-import:R0402")
      (libsource (lib "eagle-import") (part "R-EU_R0402"))
    )
    (comp (ref "R508")
      (value "47k")
      (footprint "eagle-import:R0402")
      (libsource (lib "eagle-import") (part "R-EU_R0402"))
    )
    (comp (ref "R509")
      (value "47k")
      (footprint "eagle-import:R0402")
      (libsource (lib "eagle-import") (part "R-EU_R0402"))
    )
    (comp (ref "R510")
      (value "178k")
      (footprint "eagle-import:R0402")
      (libsource (lib "eagle-import") (part "R-EU_R0402"))
    )
    (comp (ref "R511")
      (value "100k")
      (footprint "eagle-import:R0402")
      (libsource (lib "eagle-import") (part "R-EU_R0402"))
    )
    (comp (ref "R512")
      (value "47k")
      (footprint "eagle-import:R0402")
      (libsource (lib "eagle-import") (part "R-EU_R0402"))
    )
    (comp (ref "R513")
      (value "47k")
      (footprint "eagle-import:R0402")
      (libsource (lib "eagle-import") (part "R-EU_R0402"))
    )
    (comp (ref "R514")
      (value "62k")
      (footprint "eagle-import:R0402")
      (libsource (lib "eagle-import") (part "R-EU_R0402"))
    )
    (comp (ref "S501")
      (value "tbd")
      (footprint "eagle-import:434121043816")
      (libsource (lib "eagle-import") (part "434121043816"))
    )
    (comp (ref "U501")
      (value "TLV70030SOT23-5")
      (footprint "eagle-import:SOT23-5")
      (libsource (lib "eagle-import") (part "TLV70030SOT23-5"))
    )
    (comp (ref "U502")
      (value "TPS61200")
      (footprint "eagle-import:QFN14_0.5MM_TH")
      (libsource (lib "eagle-import") (part "TPS61200"))
    )
    (comp (ref "U503")
      (value "TLV70030SOT23-5")
      (footprint "eagle-import:SOT23-5")
      (libsource (lib "eagle-import") (part "TLV70030SOT23-5"))
    )
    (comp (ref "U504")
      (value "TLV70030SOT23-5")
      (footprint "eagle-import:SOT23-5")
      (libsource (lib "eagle-import") (part "TLV70030SOT23-5"))
    )
    (comp (ref "C401")
      (value "100p")
      (footprint "eagle-import:C0402")
      (libsource (lib "eagle-import") (part "C-EUC0402"))
    )
    (comp (ref "C402")
      (value "15p")
      (footprint "eagle-import:C0402")
      (libsource (lib "eagle-import") (part "C-EUC0402"))
    )
    (comp (ref "C403")
      (value "12p")
      (footprint "eagle-import:C0402")
      (libsource (lib "eagle-import") (part "C-EUC0402"))
    )
    (comp (ref "C404")
      (value "100p")
      (footprint "eagle-import:C0402")
      (libsource (lib "eagle-import") (part "C-EUC0402"))
    )
    (comp (ref "C405")
      (value "1.5p")
      (footprint "eagle-import:C0402")
      (libsource (lib "eagle-import") (part "C-EUC0402"))
    )
    (comp (ref "C406")
      (value "5p")
      (footprint "eagle-import:C0402")
      (libsource (lib "eagle-import") (part "C-EUC0402"))
    )
    (comp (ref "C407")
      (value "10p")
      (footprint "eagle-import:C0402")
      (libsource (lib "eagle-import") (part "C-EUC0402"))
    )
    (comp (ref "C408")
      (value "10p")
      (footprint "eagle-import:C0402")
      (libsource (lib "eagle-import") (part "C-EUC0402"))
    )
    (comp (ref "C409")
      (value "0.4p")
      (footprint "eagle-import:C0402")
      (libsource (lib "eagle-import") (part "C-EUC0402"))
    )
    (comp (ref "C410")
      (value "100p")
      (footprint "eagle-import:C0402")
      (libsource (lib "eagle-import") (part "C-EUC0402"))
    )
    (comp (ref "C411")
      (value "100n")
      (footprint "eagle-import:C0402")
      (libsource (lib "eagle-import") (part "C-EUC0402"))
    )
    (comp (ref "C412")
      (value "1.5p")
      (footprint "eagle-import:C0402")
      (libsource (lib "eagle-import") (part "C-EUC0402"))
    )
    (comp (ref "C413")
      (value "12p")
      (footprint "eagle-import:C0402")
      (libsource (lib "eagle-import") (part "C-EUC0402"))
    )
    (comp (ref "C414")
      (value "10n")
      (footprint "eagle-import:C0603")
      (libsource (lib "eagle-import") (part "C-EUC0603"))
    )
    (comp (ref "C415")
      (value "100n")
      (footprint "eagle-import:C0402")
      (libsource (lib "eagle-import") (part "C-EUC0402"))
    )
    (comp (ref "C416")
      (value "100p")
      (footprint "eagle-import:C0402")
      (libsource (lib "eagle-import") (part "C-EUC0402"))
    )
    (comp (ref "C417")
      (value "12p")
      (footprint "eagle-import:C0402")
      (libsource (lib "eagle-import") (part "C-EUC0402"))
    )
    (comp (ref "C418")
      (value "5p")
      (footprint "eagle-import:C0402")
      (libsource (lib "eagle-import") (part "C-EUC0402"))
    )
    (comp (ref "C419")
      (value "27p")
      (footprint "eagle-import:C0402")
      (libsource (lib "eagle-import") (part "C-EUC0402"))
    )
    (comp (ref "C420")
      (value "100p")
      (footprint "eagle-import:C0402")
      (libsource (lib "eagle-import") (part "C-EUC0402"))
    )
    (comp (ref "C421")
      (value "1u")
      (footprint "eagle-import:C0402")
      (libsource (lib "eagle-import") (part "C-EUC0402"))
    )
    (comp (ref "D401")
      (value "tbd")
      (footprint "eagle-import:DO41-10")
      (libsource (lib "eagle-import") (part "1N4004"))
    )
    (comp (ref "L401")
      (value "tbd")
      (footprint "eagle-import:0402")
      (libsource (lib "eagle-import") (part "L0402"))
    )
    (comp (ref "L402")
      (value "tbd")
      (footprint "eagle-import:0402")
      (libsource (lib "eagle-import") (part "L0402"))
    )
    (comp (ref "L403")
      (value "tbd")
      (footprint "eagle-import:0402")
      (libsource (lib "eagle-import") (part "L0402"))
    )
    (comp (ref "L404")
      (value "tbd")
      (footprint "eagle-import:0402")
      (libsource (lib "eagle-import") (part "L0402"))
    )
    (comp (ref "L405")
      (value "tbd")
      (footprint "eagle-import:0402")
      (libsource (lib "eagle-import") (part "L0402"))
    )
    (comp (ref "L406")
      (value "tbd")
      (footprint "eagle-import:0402")
      (libsource (lib "eagle-import") (part "L0402"))
    )
    (comp (ref "L407")
      (value "tbd")
      (footprint "eagle-import:0402")
      (libsource (lib "eagle-import") (part "L0402"))
    )
    (comp (ref "L408")
      (value "tbd")
      (footprint "eagle-import:0402")
      (libsource (lib "eagle-import") (part "L0402"))
    )
    (comp (ref "L409")
      (value "1u")
      (footprint "eagle-import:0402")
      (libsource (lib "eagle-import") (part "L0402"))
    )
    (comp (ref "L410")
      (value "2.7u")
      (footprint "eagle-import:0402")
      (libsource (lib "eagle-import") (part "L0402"))
    )
    (comp (ref "R401")
      (value "51R")
      (footprint "eagle-import:R0402")
      (libsource (lib "eagle-import") (part "R-EU_R0402"))
    )
    (comp (ref "R403")
      (value "68R")
      (footprint "eagle-import:R0402")
      (libsource (lib "eagle-import") (part "R-EU_R0402"))
    )
    (comp (ref "R405")
      (value "0")
      (footprint "eagle-import:R0402")
      (libsource (lib "eagle-import") (part "R-EU_R0402"))
    )
    (comp (ref "R406")
      (value "10k")
      (footprint "eagle-import:R0402")
      (libsource (lib "eagle-import") (part "R-EU_R0402"))
    )
    (comp (ref "TP1")
      (value "TPPAD1-13")
      (footprint "eagle-import:P1-13")
      (libsource (lib "eagle-import") (part "TPPAD1-13"))
    )
    (comp (ref "U401")
      (value "SI4032QFN204X4")
      (footprint "eagle-import:QFN20_0.5MM")
      (libsource (lib "eagle-import") (part "SI4032QFN204X4"))
    )
    (comp (ref "A301")
      (value "ANT_GPSCHIPANT")
      (footprint "eagle-import:DFN100X60X40-3")
      (libsource (lib "eagle-import") (part "ANT_GPSCHIPANT"))
    )
    (comp (ref "C301")
      (value "1u")
      (footprint "eagle-import:C0402")
      (libsource (lib "eagle-import") (part "C-EUC0402"))
    )
    (comp (ref "C302")
      (value "100n")
      (footprint "eagle-import:C0402")
      (libsource (lib "eagle-import") (part "C-EUC0402"))
    )
    (comp (ref "C303")
      (value "1u")
      (footprint "eagle-import:C0402")
      (libsource (lib "eagle-import") (part "C-EUC0402"))
    )
    (comp (ref "C304")
      (value "1u")
      (footprint "eagle-import:C0402")
      (libsource (lib "eagle-import") (part "C-EUC0402"))
    )
    (comp (ref "C305")
      (value "1u")
      (footprint "eagle-import:C0402")
      (libsource (lib "eagle-import") (part "C-EUC0402"))
    )
    (comp (ref "C306")
      (value "1n")
      (footprint "eagle-import:C0402")
      (libsource (lib "eagle-import") (part "C-EUC0402"))
    )
    (comp (ref "C307")
      (value "100n")
      (footprint "eagle-import:C0402")
      (libsource (lib "eagle-import") (part "C-EUC0402"))
    )
    (comp (ref "C308")
      (value "15p")
      (footprint "eagle-import:C0402")
      (libsource (lib "eagle-import") (part "C-EUC0402"))
    )
    (comp (ref "C309")
      (value "1u")
      (footprint "eagle-import:C0402")
      (libsource (lib "eagle-import") (part "C-EUC0402"))
    )
    (comp (ref "C310")
      (value "6p")
      (footprint "eagle-import:C0402")
      (libsource (lib "eagle-import") (part "C-EUC0402"))
    )
    (comp (ref "C311")
      (value "1u")
      (footprint "eagle-import:C0402")
      (libsource (lib "eagle-import") (part "C-EUC0402"))
    )
    (comp (ref "C312")
      (value "2.2u")
      (footprint "eagle-import:C0603")
      (libsource (lib "eagle-import") (part "C-EUC0603"))
    )
    (comp (ref "C313")
      (value "1u")
      (footprint "eagle-import:C0402")
      (libsource (lib "eagle-import") (part "C-EUC0402"))
    )
    (comp (ref "C314")
      (value "2.2u")
      (footprint "eagle-import:C0603")
      (libsource (lib "eagle-import") (part "C-EUC0603"))
    )
    (comp (ref "C315")
      (value "1u")
      (footprint "eagle-import:C0402")
      (libsource (lib "eagle-import") (part "C-EUC0402"))
    )
    (comp (ref "C316")
      (value "1u")
      (footprint "eagle-import:C0402")
      (libsource (lib "eagle-import") (part "C-EUC0402"))
    )
    (comp (ref "C317")
      (value "12p")
      (footprint "eagle-import:C0402")
      (libsource (lib "eagle-import") (part "C-EUC0402"))
    )
    (comp (ref "C318")
      (value "12p")
      (footprint "eagle-import:C0402")
      (libsource (lib "eagle-import") (part "C-EUC0402"))
    )
    (comp (ref "C319")
      (value "1u")
      (footprint "eagle-import:C0402")
      (libsource (lib "eagle-import") (part "C-EUC0402"))
    )
    (comp (ref "L301")
      (value "tbd")
      (footprint "eagle-import:0402")
      (libsource (lib "eagle-import") (part "L0402"))
    )
    (comp (ref "L302")
      (value "tbd")
      (footprint "eagle-import:0402")
      (libsource (lib "eagle-import") (part "L0402"))
    )
    (comp (ref "L303")
      (value "tbd")
      (footprint "eagle-import:0402")
      (libsource (lib "eagle-import") (part "L0402"))
    )
    (comp (ref "L304")
      (value "tbd")
      (footprint "eagle-import:0402")
      (libsource (lib "eagle-import") (part "L0402"))
    )
    (comp (ref "L305")
      (value "2.7u")
      (footprint "eagle-import:0402")
      (libsource (lib "eagle-import") (part "L0402"))
    )
    (comp (ref "L306")
      (value "2.7u")
      (footprint "eagle-import:0402")
      (libsource (lib "eagle-import") (part "L0402"))
    )
    (comp (ref "R303")
      (value "47k")
      (footprint "eagle-import:R0402")
      (libsource (lib "eagle-import") (part "R-EU_R0402"))
    )
    (comp (ref "R304")
      (value "0")
      (footprint "eagle-import:R0402")
      (libsource (lib "eagle-import") (part "R-EU_R0402"))
    )
    (comp (ref "R305")
      (value "100R")
      (footprint "eagle-import:R0402")
      (libsource (lib "eagle-import") (part "R-EU_R0402"))
    )
    (comp (ref "R306")
      (value "100R")
      (footprint "eagle-import:R0402")
      (libsource (lib "eagle-import") (part "R-EU_R0402"))
    )
    (comp (ref "R307")
      (value "100R")
      (footprint "eagle-import:R0402")
      (libsource (lib "eagle-import") (part "R-EU_R0402"))
    )
    (comp (ref "R308")
      (value "3.9k")
      (footprint "eagle-import:R0402")
      (libsource (lib "eagle-import") (part "R-EU_R0402"))
    )
    (comp (ref "R309")
      (value "68R")
      (footprint "eagle-import:R0402")
      (libsource (lib "eagle-import") (part "R-EU_R0402"))
    )
    (comp (ref "U301")
      (value "DIFFGEN")
      (footprint "eagle-import:SOT23-5")
      (libsource (lib "eagle-import") (part "DIFFGEN"))
    )
    (comp (ref "U302")
      (value "UBX-6010MLF56")
      (footprint "eagle-import:QFN56_0.5MM")
      (libsource (lib "eagle-import") (part "UBX-6010MLF56"))
    )
    (comp (ref "U303")
      (value "SAW")
      (footprint "eagle-import:SOT23-5")
      (libsource (lib "eagle-import") (part "SAW"))
    )
    (comp (ref "U304")
      (value "LNA")
      (footprint "eagle-import:SOT23-6")
      (libsource (lib "eagle-import") (part "LNA"))
    )
    (comp (ref "X301")
      (value "tbd")
      (footprint "eagle-import:OSCCC650X400X120")
      (libsource (lib "eagle-import") (part "OSC_GPSXTAL4"))
    )
  )
  (nets
    (net (code "1") (name "+3V_ANA") (class "Default")
      (node (ref "C201") (pin "1") (pinfunction "1_1") (pintype "passive"))
      (node (ref "C202") (pin "1") (pinfunction "1_1") (pintype "passive"))
      (node (ref "C203") (pin "1") (pinfunction "1_1") (pintype "passive"))
      (node (ref "C204") (pin "1") (pinfunction "1_1") (pintype "passive"))
      (node (ref "C205") (pin "1") (pinfunction "1_1") (pintype "passive"))
      (node (ref "C206") (pin "1") (pinfunction "1_1") (pintype "passive"))
      (node (ref "C514") (pin "1") (pinfunction "1_1") (pintype "passive"))
      (node (ref "C515") (pin "1") (pinfunction "1_1") (pintype "passive"))
      (node (ref "Q201") (pin "2") (pinfunction "D_2") (pintype "passive"))
      (node (ref "Q202") (pin "2") (pinfunction "D_2") (pintype "passive"))
      (node (ref "R206") (pin "2") (pinfunction "2_2") (pintype "passive"))
      (node (ref "U201") (pin "14") (pinfunction "VCC_14") (pintype "bidirectional"))
      (node (ref "U202") (pin "2") (pinfunction "VCC_2") (pintype "bidirectional"))
      (node (ref "U203") (pin "2") (pinfunction "VCC_2") (pintype "bidirectional"))
      (node (ref "U204") (pin "2") (pinfunction "VCC_2") (pintype "bidirectional"))
      (node (ref "U205") (pin "14") (pinfunction "VCC_14") (pintype "bidirectional"))
      (node (ref "U207") (pin "8") (pinfunction "VCC_8") (pintype "bidirectional"))
      (node (ref "U503") (pin "5") (pinfunction "OUT_5") (pintype "bidirectional"))
    )
    (net (code "2") (name "+3V_GPS") (class "Default")
      (node (ref "C319") (pin "2") (pinfunction "2_2") (pintype "passive"))
      (node (ref "C521") (pin "1") (pinfunction "1_1") (pintype "passive"))
      (node (ref "L305") (pin "1") (pinfunction "1_1") (pintype "passive"))
      (node (ref "L306") (pin "1") (pinfunction "1_1") (pintype "passive"))
      (node (ref "R308") (pin "1") (pinfunction "1_1") (pintype "passive"))
      (node (ref "U302") (pin "25") (pinfunction "V_DCDC_25") (pintype "bidirectional"))
      (node (ref "U504") (pin "5") (pinfunction "OUT_5") (pintype "bidirectional"))
    )
    (net (code "3") (name "+3V_MCU") (class "Default")
      (node (ref "C101") (pin "2") (pinfunction "2_2") (pintype "passive"))
      (node (ref "C102") (pin "2") (pinfunction "2_2") (pintype "passive"))
      (node (ref "C103") (pin "2") (pinfunction "2_2") (pintype "passive"))
      (node (ref "C104") (pin "2") (pinfunction "2_2") (pintype "passive"))
      (node (ref "C105") (pin "2") (pinfunction "2_2") (pintype "passive"))
      (node (ref "C106") (pin "2") (pinfunction "2_2") (pintype "passive"))
      (node (ref "C107") (pin "2") (pinfunction "2_2") (pintype "passive"))
      (node (ref "C108") (pin "2") (pinfunction "2_2") (pintype "passive"))
      (node (ref "C309") (pin "2") (pinfunction "2_2") (pintype "passive"))
      (node (ref "C315") (pin "2") (pinfunction "2_2") (pintype "passive"))
      (node (ref "C316") (pin "1") (pinfunction "1_1") (pintype "passive"))
      (node (ref "C413") (pin "1") (pinfunction "1_1") (pintype "passive"))
      (node (ref "C502") (pin "1") (pinfunction "1_1") (pintype "passive"))
      (node (ref "C503") (pin "1") (pinfunction "1_1") (pintype "passive"))
      (node (ref "C601") (pin "1") (pinfunction "1_1") (pintype "passive"))
      (node (ref "D601") (pin "C") (pinfunction "C_C") (pintype "passive"))
      (node (ref "J601") (pin "2") (pinfunction "16_2") (pintype "passive"))
      (node (ref "J602") (pin "4") (pinfunction "9_4") (pintype "passive"))
      (node (ref "L409") (pin "1") (pinfunction "1_1") (pintype "passive"))
      (node (ref "L410") (pin "2") (pinfunction "2_2") (pintype "passive"))
      (node (ref "R601") (pin "2") (pinfunction "2_2") (pintype "passive"))
      (node (ref "R607") (pin "2") (pinfunction "2_2") (pintype "passive"))
      (node (ref "R608") (pin "2") (pinfunction "2_2") (pintype "passive"))
      (node (ref "U101") (pin "24") (pinfunction "VDD1_24") (pintype "bidirectional"))
      (node (ref "U101") (pin "36") (pinfunction "VDD2_36") (pintype "bidirectional"))
      (node (ref "U101") (pin "48") (pinfunction "VDD3_48") (pintype "bidirectional"))
      (node (ref "U101") (pin "9") (pinfunction "VDDA_9") (pintype "bidirectional"))
      (node (ref "U302") (pin "15") (pinfunction "VDD_IO_15") (pintype "bidirectional"))
      (node (ref "U302") (pin "29") (pinfunction "V_RUN_29") (pintype "bidirectional"))
      (node (ref "U302") (pin "42") (pinfunction "VDD_IO1_42") (pintype "bidirectional"))
      (node (ref "U501") (pin "5") (pinfunction "OUT_5") (pintype "bidirectional"))
      (node (ref "U601") (pin "3") (pinfunction "~{WP}_3") (pintype "input"))
      (node (ref "U601") (pin "7") (pinfunction "~{HOLD}_7") (pintype "input"))
      (node (ref "U601") (pin "8") (pinfunction "VCC_8") (pintype "power_in"))
    )
    (net (code "4") (name "BAT_SW") (class "Default")
      (node (ref "C504") (pin "1") (pinfunction "1_1") (pintype "passive"))
      (node (ref "C505") (pin "1") (pinfunction "1_1") (pintype "passive"))
      (node (ref "Q501") (pin "1") (pinfunction "G_1") (pintype "passive"))
      (node (ref "Q502") (pin "3") (pinfunction "D_3") (pintype "passive"))
      (node (ref "R501") (pin "2") (pinfunction "2_2") (pintype "passive"))
    )
    (net (code "5") (name "CS_PRESSURE") (class "Default")
      (node (ref "J601") (pin "14") (pinfunction "10_14") (pintype "passive"))
    )
    (net (code "6") (name "CS_RADIO") (class "Default")
      (node (ref "U101") (pin "2") (pinfunction "PC13_2") (pintype "bidirectional"))
      (node (ref "U401") (pin "16") (pinfunction "NSEL_16") (pintype "bidirectional"))
    )
    (net (code "7") (name "FRONTEND_UNKNOWN") (class "Default")
      (node (ref "C114") (pin "1") (pinfunction "1_1") (pintype "passive"))
      (node (ref "R106") (pin "1") (pinfunction "1_1") (pintype "passive"))
      (node (ref "R124") (pin "1") (pinfunction "1_1") (pintype "passive"))
      (node (ref "R206") (pin "1") (pinfunction "1_1") (pintype "passive"))
    )
    (net (code "8") (name "GND") (class "Default")
      (node (ref "A301") (pin "2") (pinfunction "GND_2") (pintype "bidirectional"))
      (node (ref "A301") (pin "3") (pinfunction "GND_3") (pintype "bidirectional"))
      (node (ref "C101") (pin "1") (pinfunction "1_1") (pintype "passive"))
      (node (ref "C102") (pin "1") (pinfunction "1_1") (pintype "passive"))
      (node (ref "C103") (pin "1") (pinfunction "1_1") (pintype "passive"))
      (node (ref "C104") (pin "1") (pinfunction "1_1") (pintype "passive"))
      (node (ref "C105") (pin "1") (pinfunction "1_1") (pintype "passive"))
      (node (ref "C106") (pin "1") (pinfunction "1_1") (pintype "passive"))
      (node (ref "C107") (pin "1") (pinfunction "1_1") (pintype "passive"))
      (node (ref "C108") (pin "1") (pinfunction "1_1") (pintype "passive"))
      (node (ref "C109") (pin "2") (pinfunction "2_2") (pintype "passive"))
      (node (ref "C110") (pin "2") (pinfunction "2_2") (pintype "passive"))
      (node (ref "C111") (pin "2") (pinfunction "2_2") (pintype "passive"))
      (node (ref "C112") (pin "2") (pinfunction "2_2") (pintype "passive"))
      (node (ref "C113") (pin "2") (pinfunction "2_2") (pintype "passive"))
      (node (ref "C114") (pin "2") (pinfunction "2_2") (pintype "passive"))
      (node (ref "C115") (pin "2") (pinfunction "2_2") (pintype "passive"))
      (node (ref "C116") (pin "1") (pinfunction "1_1") (pintype "passive"))
      (node (ref "C117") (pin "1") (pinfunction "1_1") (pintype "passive"))
      (node (ref "C118") (pin "1") (pinfunction "1_1") (pintype "passive"))
      (node (ref "C119") (pin "1") (pinfunction "1_1") (pintype "passive"))
      (node (ref "C120") (pin "1") (pinfunction "1_1") (pintype "passive"))
      (node (ref "C121") (pin "1") (pinfunction "1_1") (pintype "passive"))
      (node (ref "C122") (pin "1") (pinfunction "1_1") (pintype "passive"))
      (node (ref "C123") (pin "1") (pinfunction "1_1") (pintype "passive"))
      (node (ref "C124") (pin "1") (pinfunction "1_1") (pintype "passive"))
      (node (ref "C201") (pin "2") (pinfunction "2_2") (pintype "passive"))
      (node (ref "C202") (pin "2") (pinfunction "2_2") (pintype "passive"))
      (node (ref "C203") (pin "2") (pinfunction "2_2") (pintype "passive"))
      (node (ref "C204") (pin "2") (pinfunction "2_2") (pintype "passive"))
      (node (ref "C205") (pin "2") (pinfunction "2_2") (pintype "passive"))
      (node (ref "C206") (pin "2") (pinfunction "2_2") (pintype "passive"))
      (node (ref "C210") (pin "2") (pinfunction "2_2") (pintype "passive"))
      (node (ref "C211") (pin "2") (pinfunction "2_2") (pintype "passive"))
      (node (ref "C214") (pin "2") (pinfunction "2_2") (pintype "passive"))
      (node (ref "C218") (pin "2") (pinfunction "2_2") (pintype "passive"))
      (node (ref "C219") (pin "2") (pinfunction "2_2") (pintype "passive"))
      (node (ref "C220") (pin "2") (pinfunction "2_2") (pintype "passive"))
      (node (ref "C221") (pin "2") (pinfunction "2_2") (pintype "passive"))
      (node (ref "C301") (pin "2") (pinfunction "2_2") (pintype "passive"))
      (node (ref "C302") (pin "2") (pinfunction "2_2") (pintype "passive"))
      (node (ref "C303") (pin "1") (pinfunction "1_1") (pintype "passive"))
      (node (ref "C304") (pin "1") (pinfunction "1_1") (pintype "passive"))
      (node (ref "C305") (pin "1") (pinfunction "1_1") (pintype "passive"))
      (node (ref "C306") (pin "2") (pinfunction "2_2") (pintype "passive"))
      (node (ref "C307") (pin "2") (pinfunction "2_2") (pintype "passive"))
      (node (ref "C309") (pin "1") (pinfunction "1_1") (pintype "passive"))
      (node (ref "C310") (pin "2") (pinfunction "2_2") (pintype "passive"))
      (node (ref "C312") (pin "1") (pinfunction "1_1") (pintype "passive"))
      (node (ref "C313") (pin "1") (pinfunction "1_1") (pintype "passive"))
      (node (ref "C314") (pin "1") (pinfunction "1_1") (pintype "passive"))
      (node (ref "C315") (pin "1") (pinfunction "1_1") (pintype "passive"))
      (node (ref "C316") (pin "2") (pinfunction "2_2") (pintype "passive"))
      (node (ref "C317") (pin "1") (pinfunction "1_1") (pintype "passive"))
      (node (ref "C318") (pin "1") (pinfunction "1_1") (pintype "passive"))
      (node (ref "C319") (pin "1") (pinfunction "1_1") (pintype "passive"))
      (node (ref "C406") (pin "2") (pinfunction "2_2") (pintype "passive"))
      (node (ref "C407") (pin "2") (pinfunction "2_2") (pintype "passive"))
      (node (ref "C408") (pin "2") (pinfunction "2_2") (pintype "passive"))
      (node (ref "C409") (pin "1") (pinfunction "1_1") (pintype "passive"))
      (node (ref "C410") (pin "2") (pinfunction "2_2") (pintype "passive"))
      (node (ref "C411") (pin "2") (pinfunction "2_2") (pintype "passive"))
      (node (ref "C412") (pin "2") (pinfunction "2_2") (pintype "passive"))
      (node (ref "C413") (pin "2") (pinfunction "2_2") (pintype "passive"))
      (node (ref "C414") (pin "2") (pinfunction "2_2") (pintype "passive"))
      (node (ref "C415") (pin "2") (pinfunction "2_2") (pintype "passive"))
      (node (ref "C416") (pin "2") (pinfunction "2_2") (pintype "passive"))
      (node (ref "C417") (pin "2") (pinfunction "2_2") (pintype "passive"))
      (node (ref "C418") (pin "2") (pinfunction "2_2") (pintype "passive"))
      (node (ref "C419") (pin "2") (pinfunction "2_2") (pintype "passive"))
      (node (ref "C420") (pin "2") (pinfunction "2_2") (pintype "passive"))
      (node (ref "C421") (pin "2") (pinfunction "2_2") (pintype "passive"))
      (node (ref "C501") (pin "2") (pinfunction "2_2") (pintype "passive"))
      (node (ref "C502") (pin "2") (pinfunction "2_2") (pintype "passive"))
      (node (ref "C503") (pin "2") (pinfunction "2_2") (pintype "passive"))
      (node (ref "C506") (pin "2") (pinfunction "2_2") (pintype "passive"))
      (node (ref "C507") (pin "2") (pinfunction "2_2") (pintype "passive"))
      (node (ref "C508") (pin "2") (pinfunction "2_2") (pintype "passive"))
      (node (ref "C509") (pin "2") (pinfunction "2_2") (pintype "passive"))
      (node (ref "C510") (pin "2") (pinfunction "2_2") (pintype "passive"))
      (node (ref "C511") (pin "2") (pinfunction "2_2") (pintype "passive"))
      (node (ref "C512") (pin "2") (pinfunction "2_2") (pintype "passive"))
      (node (ref "C513") (pin "2") (pinfunction "2_2") (pintype "passive"))
      (node (ref "C514") (pin "2") (pinfunction "2_2") (pintype "passive"))
      (node (ref "C515") (pin "2") (pinfunction "2_2") (pintype "passive"))
      (node (ref "C516") (pin "2") (pinfunction "2_2") (pintype "passive"))
      (node (ref "C517") (pin "2") (pinfunction "2_2") (pintype "passive"))
      (node (ref "C518") (pin "2") (pinfunction "2_2") (pintype "passive"))
      (node (ref "C519") (pin "2") (pinfunction "2_2") (pintype "passive"))
      (node (ref "C520") (pin "2") (pinfunction "2_2") (pintype "passive"))
      (node (ref "C521") (pin "2") (pinfunction "2_2") (pintype "passive"))
      (node (ref "C522") (pin "2") (pinfunction "2_2") (pintype "passive"))
      (node (ref "C523") (pin "2") (pinfunction "2_2") (pintype "passive"))
      (node (ref "C524") (pin "2") (pinfunction "2_2") (pintype "passive"))
      (node (ref "C525") (pin "2") (pinfunction "2_2") (pintype "passive"))
      (node (ref "C526") (pin "2") (pinfunction "2_2") (pintype "passive"))
      (node (ref "C601") (pin "2") (pinfunction "2_2") (pintype "passive"))
      (node (ref "C603") (pin "1") (pinfunction "1_1") (pintype "passive"))
      (node (ref "C606") (pin "1") (pinfunction "1_1") (pintype "passive"))
      (node (ref "C607") (pin "1") (pinfunction "1_1") (pintype "passive"))
      (node (ref "D401") (pin "A") (pinfunction "A_A") (pintype "passive"))
      (node (ref "D501") (pin "A") (pinfunction "A_A") (pintype "passive"))
      (node (ref "D602") (pin "1") (pinfunction "A_1") (pintype "bidirectional"))
      (node (ref "D603") (pin "A") (pinfunction "A_A") (pintype "passive"))
      (node (ref "D604") (pin "A") (pinfunction "A_A") (pintype "passive"))
      (node (ref "D605") (pin "A") (pinfunction "A_A") (pintype "passive"))
      (node (ref "D606") (pin "A") (pinfunction "A_A") (pintype "passive"))
      (node (ref "D607") (pin "1") (pinfunction "A_1") (pintype "bidirectional"))
      (node (ref "G501") (pin "-") (pinfunction "-_-") (pintype "passive"))
      (node (ref "J201") (pin "1") (pinfunction "GND_1") (pintype "bidirectional"))
      (node (ref "J201") (pin "10") (pinfunction "GND_10") (pintype "bidirectional"))
      (node (ref "J201") (pin "12") (pinfunction "GND_12") (pintype "bidirectional"))
      (node (ref "J201") (pin "14") (pinfunction "GND_14") (pintype "bidirectional"))
      (node (ref "J201") (pin "15") (pinfunction "GND_15") (pintype "bidirectional"))
      (node (ref "J201") (pin "16") (pinfunction "GND_16") (pintype "bidirectional"))
      (node (ref "J201") (pin "3") (pinfunction "GND_3") (pintype "bidirectional"))
      (node (ref "J201") (pin "5") (pinfunction "GND_5") (pintype "bidirectional"))
      (node (ref "J201") (pin "7") (pinfunction "GND_7") (pintype "bidirectional"))
      (node (ref "J201") (pin "Z1") (pinfunction "GND_Z1") (pintype "bidirectional"))
      (node (ref "J201") (pin "Z2") (pinfunction "GND_Z2") (pintype "bidirectional"))
      (node (ref "J201") (pin "Z3") (pinfunction "GND_Z3") (pintype "bidirectional"))
      (node (ref "J201") (pin "Z4") (pinfunction "GND_Z4") (pintype "bidirectional"))
      (node (ref "J601") (pin "1") (pinfunction "1_1") (pintype "passive"))
      (node (ref "J601") (pin "12") (pinfunction "11_12") (pintype "passive"))
      (node (ref "J601") (pin "16") (pinfunction "9_16") (pintype "passive"))
      (node (ref "J602") (pin "1") (pinfunction "1_1") (pintype "passive"))
      (node (ref "J602") (pin "10") (pinfunction "6_10") (pintype "passive"))
      (node (ref "L304") (pin "1") (pinfunction "1_1") (pintype "passive"))
      (node (ref "L407") (pin "1") (pinfunction "1_1") (pintype "passive"))
      (node (ref "Q203") (pin "1") (pinfunction "S_1") (pintype "passive"))
      (node (ref "Q204") (pin "1") (pinfunction "S_1") (pintype "passive"))
      (node (ref "Q502") (pin "1") (pinfunction "S_1") (pintype "passive"))
      (node (ref "Q503") (pin "1") (pinfunction "S_1") (pintype "passive"))
      (node (ref "Q601") (pin "1") (pinfunction "S_1") (pintype "passive"))
      (node (ref "R124") (pin "2") (pinfunction "2_2") (pintype "passive"))
      (node (ref "R125") (pin "2") (pinfunction "2_2") (pintype "passive"))
      (node (ref "R126") (pin "2") (pinfunction "2_2") (pintype "passive"))
      (node (ref "R209") (pin "2") (pinfunction "2_2") (pintype "passive"))
      (node (ref "R303") (pin "2") (pinfunction "2_2") (pintype "passive"))
      (node (ref "R401") (pin "1") (pinfunction "1_1") (pintype "passive"))
      (node (ref "R504") (pin "1") (pinfunction "1_1") (pintype "passive"))
      (node (ref "R511") (pin "2") (pinfunction "2_2") (pintype "passive"))
      (node (ref "R512") (pin "1") (pinfunction "1_1") (pintype "passive"))
      (node (ref "R513") (pin "1") (pinfunction "1_1") (pintype "passive"))
      (node (ref "R514") (pin "2") (pinfunction "2_2") (pintype "passive"))
      (node (ref "R603") (pin "1") (pinfunction "1_1") (pintype "passive"))
      (node (ref "R604") (pin "1") (pinfunction "1_1") (pintype "passive"))
      (node (ref "U101") (pin "23") (pinfunction "VSS1_23") (pintype "bidirectional"))
      (node (ref "U101") (pin "35") (pinfunction "VSS2_35") (pintype "bidirectional"))
      (node (ref "U101") (pin "47") (pinfunction "VSS3_47") (pintype "bidirectional"))
      (node (ref "U101") (pin "8") (pinfunction "VSSA_8") (pintype "bidirectional"))
      (node (ref "U201") (pin "7") (pinfunction "GND_7") (pintype "bidirectional"))
      (node (ref "U202") (pin "3") (pinfunction "GND_3") (pintype "bidirectional"))
      (node (ref "U202") (pin "4") (pinfunction "NC_4") (pintype "bidirectional"))
      (node (ref "U203") (pin "3") (pinfunction "GND_3") (pintype "bidirectional"))
      (node (ref "U203") (pin "4") (pinfunction "NC_4") (pintype "bidirectional"))
      (node (ref "U204") (pin "3") (pinfunction "GND_3") (pintype "bidirectional"))
      (node (ref "U204") (pin "4") (pinfunction "NC_4") (pintype "bidirectional"))
      (node (ref "U205") (pin "7") (pinfunction "GND_7") (pintype "bidirectional"))
      (node (ref "U206") (pin "2") (pinfunction "GND_2") (pintype "bidirectional"))
      (node (ref "U207") (pin "4") (pinfunction "GND_4") (pintype "bidirectional"))
      (node (ref "U208") (pin "3") (pinfunction "B_3") (pintype "bidirectional"))
      (node (ref "U301") (pin "1") (pinfunction "GND1_1") (pintype "bidirectional"))
      (node (ref "U301") (pin "2") (pinfunction "GND2_2") (pintype "bidirectional"))
      (node (ref "U302") (pin "12") (pinfunction "VDD_USB_12") (pintype "bidirectional"))
      (node (ref "U303") (pin "1") (pinfunction "GND1_1") (pintype "bidirectional"))
      (node (ref "U303") (pin "2") (pinfunction "GND2_2") (pintype "bidirectional"))
      (node (ref "U303") (pin "3") (pinfunction "GND3_3") (pintype "bidirectional"))
      (node (ref "U304") (pin "1") (pinfunction "GND1_1") (pintype "bidirectional"))
      (node (ref "U304") (pin "2") (pinfunction "GND2_2") (pintype "bidirectional"))
      (node (ref "U304") (pin "4") (pinfunction "GND3_4") (pintype "bidirectional"))
      (node (ref "U304") (pin "5") (pinfunction "GND4_5") (pintype "bidirectional"))
      (node (ref "U401") (pin "20") (pinfunction "SDN_20") (pintype "bidirectional"))
      (node (ref "U401") (pin "21") (pinfunction "EP_21") (pintype "bidirectional"))
      (node (ref "U501") (pin "2") (pinfunction "GND_2") (pintype "bidirectional"))
      (node (ref "U502") (pin "4") (pinfunction "PGND_4") (pintype "bidirectional"))
      (node (ref "U502") (pin "9") (pinfunction "GND_9") (pintype "bidirectional"))
      (node (ref "U502") (pin "TH1") (pinfunction "PGND_TH1") (pintype "bidirectional"))
      (node (ref "U502") (pin "TH2") (pinfunction "PGND_TH2") (pintype "bidirectional"))
      (node (ref "U502") (pin "TH3") (pinfunction "PGND_TH3") (pintype "bidirectional"))
      (node (ref "U502") (pin "TH4") (pinfunction "PGND_TH4") (pintype "bidirectional"))
      (node (ref "U502") (pin "TH5") (pinfunction "PGND_TH5") (pintype "bidirectional"))
      (node (ref "U503") (pin "2") (pinfunction "GND_2") (pintype "bidirectional"))
      (node (ref "U504") (pin "2") (pinfunction "GND_2") (pintype "bidirectional"))
      (node (ref "U601") (pin "4") (pinfunction "GND_4") (pintype "power_in"))
      (node (ref "X101") (pin "1") (pinfunction "GND_1") (pintype "bidirectional"))
      (node (ref "X101") (pin "4") (pinfunction "GND_4") (pintype "bidirectional"))
      (node (ref "X301") (pin "4") (pinfunction "VCC_4") (pintype "bidirectional"))
    )
    (net (code "9") (name "GPS_CLK") (class "Default")
      (node (ref "R309") (pin "2") (pinfunction "2_2") (pintype "passive"))
      (node (ref "U302") (pin "49") (pinfunction "XTAL_I_49") (pintype "bidirectional"))
      (node (ref "X301") (pin "3") (pinfunction "OUT_3") (pintype "bidirectional"))
    )
    (net (code "10") (name "GPS_RESETN") (class "Default")
      (node (ref "R308") (pin "2") (pinfunction "2_2") (pintype "passive"))
      (node (ref "U302") (pin "23") (pinfunction "V_RESET_23") (pintype "bidirectional"))
    )
    (net (code "11") (name "GPS_RESET_N") (class "Default")
      (node (ref "C115") (pin "1") (pinfunction "1_1") (pintype "passive"))
      (node (ref "R123") (pin "1") (pinfunction "1_1") (pintype "passive"))
    )
    (net (code "12") (name "GPS_RX") (class "Default")
      (node (ref "R307") (pin "2") (pinfunction "2_2") (pintype "passive"))
      (node (ref "U101") (pin "30") (pinfunction "PA9_30") (pintype "bidirectional"))
    )
    (net (code "13") (name "GPS_TX") (class "Default")
      (node (ref "R306") (pin "2") (pinfunction "2_2") (pintype "passive"))
      (node (ref "U101") (pin "31") (pinfunction "PA10_31") (pintype "bidirectional"))
    )
    (net (code "14") (name "HEAT_HUM1") (class "Default")
      (node (ref "C217") (pin "1") (pinfunction "1_1") (pintype "passive"))
      (node (ref "R110") (pin "1") (pinfunction "1_1") (pintype "passive"))
      (node (ref "R213") (pin "2") (pinfunction "2_2") (pintype "passive"))
      (node (ref "U206") (pin "1") (pinfunction "MCU1_1") (pintype "bidirectional"))
    )
    (net (code "15") (name "HEAT_HUM2") (class "Default")
      (node (ref "C123") (pin "2") (pinfunction "2_2") (pintype "passive"))
      (node (ref "R114") (pin "1") (pinfunction "1_1") (pintype "passive"))
      (node (ref "U206") (pin "3") (pinfunction "MCU2_3") (pintype "bidirectional"))
    )
    (net (code "16") (name "HEAT_REF") (class "Default")
      (node (ref "C419") (pin "1") (pinfunction "1_1") (pintype "passive"))
      (node (ref "Q203") (pin "2") (pinfunction "G_2") (pintype "passive"))
      (node (ref "Q204") (pin "2") (pinfunction "G_2") (pintype "passive"))
      (node (ref "R406") (pin "2") (pinfunction "2_2") (pintype "passive"))
    )
    (net (code "17") (name "LED_GRN") (class "Default")
      (node (ref "C121") (pin "2") (pinfunction "2_2") (pintype "passive"))
      (node (ref "D609") (pin "C") (pinfunction "C_C") (pintype "passive"))
      (node (ref "L101") (pin "2") (pinfunction "2_2") (pintype "passive"))
    )
    (net (code "18") (name "LED_RED") (class "Default")
      (node (ref "C122") (pin "2") (pinfunction "2_2") (pintype "passive"))
      (node (ref "D608") (pin "C") (pinfunction "C_C") (pintype "passive"))
      (node (ref "L102") (pin "2") (pinfunction "2_2") (pintype "passive"))
    )
    (net (code "19") (name "MCU_RST") (class "Default")
      (node (ref "D604") (pin "C") (pinfunction "C_C") (pintype "passive"))
      (node (ref "J602") (pin "7") (pinfunction "4_7") (pintype "passive"))
      (node (ref "R101") (pin "1") (pinfunction "1_1") (pintype "passive"))
    )
    (net (code "20") (name "MEAS_OUT") (class "Default")
      (node (ref "R102") (pin "1") (pinfunction "1_1") (pintype "passive"))
      (node (ref "U208") (pin "4") (pinfunction "Y_4") (pintype "output"))
    )
    (net (code "21") (name "NFC_EN") (class "Default")
      (node (ref "D607") (pin "2") (pinfunction "K_2") (pintype "bidirectional"))
      (node (ref "R506") (pin "1") (pinfunction "1_1") (pintype "passive"))
      (node (ref "R510") (pin "1") (pinfunction "1_1") (pintype "passive"))
    )
    (net (code "22") (name "NFC_IN1") (class "Default")
      (node (ref "C603") (pin "2") (pinfunction "2_2") (pintype "passive"))
      (node (ref "D601") (pin "A") (pinfunction "A_A") (pintype "passive"))
      (node (ref "R602") (pin "1") (pinfunction "1_1") (pintype "passive"))
      (node (ref "U101") (pin "32") (pinfunction "PA11_32") (pintype "bidirectional"))
    )
    (net (code "23") (name "NFC_IN2") (class "Default")
      (node (ref "C525") (pin "1") (pinfunction "1_1") (pintype "passive"))
      (node (ref "R510") (pin "2") (pinfunction "2_2") (pintype "passive"))
      (node (ref "R514") (pin "1") (pinfunction "1_1") (pintype "passive"))
      (node (ref "U101") (pin "10") (pinfunction "PA0_10") (pintype "bidirectional"))
    )
    (net (code "24") (name "NFC_OUT") (class "Default")
      (node (ref "R606") (pin "1") (pinfunction "1_1") (pintype "passive"))
      (node (ref "U101") (pin "18") (pinfunction "PB0_18") (pintype "bidirectional"))
    )
    (net (code "25") (name "Net-(A301-ANT)") (class "Default")
      (node (ref "A301") (pin "1") (pinfunction "ANT_1") (pintype "bidirectional"))
      (node (ref "C310") (pin "1") (pinfunction "1_1") (pintype "passive"))
      (node (ref "R304") (pin "2") (pinfunction "2_2") (pintype "passive"))
    )
    (net (code "26") (name "Net-(C207-Pad2)") (class "Default")
      (node (ref "C207") (pin "2") (pinfunction "2_2") (pintype "passive"))
      (node (ref "R210") (pin "1") (pinfunction "1_1") (pintype "passive"))
    )
    (net (code "27") (name "Net-(C208-Pad2)") (class "Default")
      (node (ref "C208") (pin "2") (pinfunction "2_2") (pintype "passive"))
      (node (ref "R211") (pin "2") (pinfunction "2_2") (pintype "passive"))
    )
    (net (code "28") (name "Net-(C215-Pad1)") (class "Default")
      (node (ref "C215") (pin "1") (pinfunction "1_1") (pintype "passive"))
      (node (ref "R214") (pin "2") (pinfunction "2_2") (pintype "passive"))
    )
    (net (code "29") (name "Net-(C216-Pad1)") (class "Default")
      (node (ref "C216") (pin "1") (pinfunction "1_1") (pintype "passive"))
      (node (ref "R215") (pin "1") (pinfunction "1_1") (pintype "passive"))
    )
    (net (code "30") (name "Net-(C302-Pad1)") (class "Default")
      (node (ref "C302") (pin "1") (pinfunction "1_1") (pintype "passive"))
      (node (ref "L306") (pin "2") (pinfunction "2_2") (pintype "passive"))
      (node (ref "X301") (pin "1") (pinfunction "GND1_1") (pintype "bidirectional"))
      (node (ref "X301") (pin "2") (pinfunction "GND1_2") (pintype "bidirectional"))
    )
    (net (code "31") (name "Net-(C308-Pad1)") (class "Default")
      (node (ref "C308") (pin "1") (pinfunction "1_1") (pintype "passive"))
      (node (ref "L301") (pin "1") (pinfunction "1_1") (pintype "passive"))
      (node (ref "L303") (pin "2") (pinfunction "2_2") (pintype "passive"))
    )
    (net (code "32") (name "Net-(C402-Pad1)") (class "Default")
      (node (ref "C402") (pin "1") (pinfunction "1_1") (pintype "passive"))
      (node (ref "L401") (pin "2") (pinfunction "2_2") (pintype "passive"))
      (node (ref "R401") (pin "2") (pinfunction "2_2") (pintype "passive"))
    )
    (net (code "33") (name "Net-(C402-Pad2)") (class "Default")
      (node (ref "C402") (pin "2") (pinfunction "2_2") (pintype "passive"))
      (node (ref "C404") (pin "1") (pinfunction "1_1") (pintype "passive"))
      (node (ref "D401") (pin "C") (pinfunction "C_C") (pintype "passive"))
      (node (ref "L401") (pin "1") (pinfunction "1_1") (pintype "passive"))
      (node (ref "L405") (pin "2") (pinfunction "2_2") (pintype "passive"))
    )
    (net (code "34") (name "Net-(C403-Pad1)") (class "Default")
      (node (ref "C403") (pin "1") (pinfunction "1_1") (pintype "passive"))
      (node (ref "C405") (pin "2") (pinfunction "2_2") (pintype "passive"))
      (node (ref "L402") (pin "2") (pinfunction "2_2") (pintype "passive"))
      (node (ref "L407") (pin "2") (pinfunction "2_2") (pintype "passive"))
    )
    (net (code "35") (name "Net-(C403-Pad2)") (class "Default")
      (node (ref "C403") (pin "2") (pinfunction "2_2") (pintype "passive"))
      (node (ref "C406") (pin "1") (pinfunction "1_1") (pintype "passive"))
      (node (ref "L403") (pin "1") (pinfunction "1_1") (pintype "passive"))
    )
    (net (code "36") (name "Net-(C407-Pad1)") (class "Default")
      (node (ref "C407") (pin "1") (pinfunction "1_1") (pintype "passive"))
      (node (ref "L403") (pin "2") (pinfunction "2_2") (pintype "passive"))
      (node (ref "L404") (pin "1") (pinfunction "1_1") (pintype "passive"))
    )
    (net (code "37") (name "Net-(C408-Pad1)") (class "Default")
      (node (ref "C408") (pin "1") (pinfunction "1_1") (pintype "passive"))
      (node (ref "L404") (pin "2") (pinfunction "2_2") (pintype "passive"))
      (node (ref "L405") (pin "1") (pinfunction "1_1") (pintype "passive"))
    )
    (net (code "38") (name "Net-(C412-Pad1)") (class "Default")
      (node (ref "C412") (pin "1") (pinfunction "1_1") (pintype "passive"))
      (node (ref "L406") (pin "1") (pinfunction "1_1") (pintype "passive"))
    )
    (net (code "39") (name "Net-(C418-Pad1)") (class "Default")
      (node (ref "C418") (pin "1") (pinfunction "1_1") (pintype "passive"))
      (node (ref "L408") (pin "1") (pinfunction "1_1") (pintype "passive"))
      (node (ref "R405") (pin "1") (pinfunction "1_1") (pintype "passive"))
    )
    (net (code "40") (name "Net-(C602-Pad2)") (class "Default")
      (node (ref "C602") (pin "2") (pinfunction "2_2") (pintype "passive"))
      (node (ref "R601") (pin "1") (pinfunction "1_1") (pintype "passive"))
      (node (ref "R602") (pin "2") (pinfunction "2_2") (pintype "passive"))
      (node (ref "R604") (pin "2") (pinfunction "2_2") (pintype "passive"))
    )
    (net (code "41") (name "Net-(D502-PadA)") (class "Default")
      (node (ref "D502") (pin "A") (pinfunction "A_A") (pintype "passive"))
      (node (ref "R506") (pin "2") (pinfunction "2_2") (pintype "passive"))
    )
    (net (code "42") (name "Net-(D602-K)") (class "Default")
      (node (ref "C602") (pin "1") (pinfunction "1_1") (pintype "passive"))
      (node (ref "D602") (pin "2") (pinfunction "K_2") (pintype "bidirectional"))
      (node (ref "D603") (pin "C") (pinfunction "C_C") (pintype "passive"))
      (node (ref "R603") (pin "2") (pinfunction "2_2") (pintype "passive"))
    )
    (net (code "43") (name "Net-(D602-M)") (class "Default")
      (node (ref "C604") (pin "1") (pinfunction "1_1") (pintype "passive"))
      (node (ref "C604") (pin "2") (pinfunction "2_2") (pintype "passive"))
      (node (ref "C605") (pin "1") (pinfunction "1_1") (pintype "passive"))
      (node (ref "C605") (pin "2") (pinfunction "2_2") (pintype "passive"))
      (node (ref "D602") (pin "3") (pinfunction "M_3") (pintype "bidirectional"))
      (node (ref "D607") (pin "3") (pinfunction "M_3") (pintype "bidirectional"))
      (node (ref "R605") (pin "2") (pinfunction "2_2") (pintype "passive"))
    )
    (net (code "44") (name "Net-(D608-PadA)") (class "Default")
      (node (ref "D608") (pin "A") (pinfunction "A_A") (pintype "passive"))
      (node (ref "R607") (pin "1") (pinfunction "1_1") (pintype "passive"))
    )
    (net (code "45") (name "Net-(D609-PadA)") (class "Default")
      (node (ref "D609") (pin "A") (pinfunction "A_A") (pintype "passive"))
      (node (ref "R608") (pin "1") (pinfunction "1_1") (pintype "passive"))
    )
    (net (code "46") (name "Net-(F501-Pad1)") (class "Default")
      (node (ref "F501") (pin "1") (pinfunction "1_1") (pintype "passive"))
      (node (ref "G501") (pin "+") (pinfunction "+_+") (pintype "passive"))
    )
    (net (code "47") (name "Net-(J201B-1)") (class "Default")
      (node (ref "C217") (pin "2") (pinfunction "2_2") (pintype "passive"))
      (node (ref "J201") (pin "8") (pinfunction "1_8") (pintype "passive"))
      (node (ref "R213") (pin "1") (pinfunction "1_1") (pintype "passive"))
      (node (ref "R216") (pin "2") (pinfunction "2_2") (pintype "passive"))
      (node (ref "R217") (pin "2") (pinfunction "2_2") (pintype "passive"))
      (node (ref "R218") (pin "2") (pinfunction "2_2") (pintype "passive"))
      (node (ref "U206") (pin "6") (pinfunction "SENSE3_6") (pintype "bidirectional"))
    )
    (net (code "48") (name "Net-(J201C-1)") (class "Default")
      (node (ref "C208") (pin "1") (pinfunction "1_1") (pintype "passive"))
      (node (ref "C209") (pin "1") (pinfunction "1_1") (pintype "passive"))
      (node (ref "C210") (pin "1") (pinfunction "1_1") (pintype "passive"))
      (node (ref "C211") (pin "1") (pinfunction "1_1") (pintype "passive"))
      (node (ref "C213") (pin "1") (pinfunction "1_1") (pintype "passive"))
      (node (ref "J201") (pin "4") (pinfunction "1_4") (pintype "passive"))
      (node (ref "Q202") (pin "3") (pinfunction "S_3") (pintype "passive"))
      (node (ref "R204") (pin "2") (pinfunction "2_2") (pintype "passive"))
      (node (ref "R205") (pin "2") (pinfunction "2_2") (pintype "passive"))
      (node (ref "R212") (pin "2") (pinfunction "2_2") (pintype "passive"))
      (node (ref "U205") (pin "1") (pinfunction "A_1") (pintype "bidirectional"))
    )
    (net (code "49") (name "Net-(J201C-2)") (class "Default")
      (node (ref "J201") (pin "6") (pinfunction "2_6") (pintype "passive"))
      (node (ref "U203") (pin "5") (pinfunction "COM_5") (pintype "bidirectional"))
    )
    (net (code "50") (name "Net-(J201D-HYG_TEMP)") (class "Default")
      (node (ref "J201") (pin "11") (pinfunction "HYG_TEMP_11") (pintype "passive"))
      (node (ref "U201") (pin "8") (pinfunction "NO_8") (pintype "bidirectional"))
    )
    (net (code "51") (name "Net-(J201D-TEMP)") (class "Default")
      (node (ref "J201") (pin "2") (pinfunction "TEMP_2") (pintype "passive"))
      (node (ref "U201") (pin "11") (pinfunction "NO_11") (pintype "bidirectional"))
    )
    (net (code "52") (name "Net-(J201D-TEMP_COM)") (class "Default")
      (node (ref "C207") (pin "1") (pinfunction "1_1") (pintype "passive"))
      (node (ref "C212") (pin "1") (pinfunction "1_1") (pintype "passive"))
      (node (ref "C220") (pin "1") (pinfunction "1_1") (pintype "passive"))
      (node (ref "C221") (pin "1") (pinfunction "1_1") (pintype "passive"))
      (node (ref "J201") (pin "13") (pinfunction "TEMP_COM_13") (pintype "passive"))
      (node (ref "Q201") (pin "3") (pinfunction "S_3") (pintype "passive"))
      (node (ref "R201") (pin "2") (pinfunction "2_2") (pintype "passive"))
      (node (ref "R202") (pin "2") (pinfunction "2_2") (pintype "passive"))
      (node (ref "R203") (pin "2") (pinfunction "2_2") (pintype "passive"))
      (node (ref "R207") (pin "1") (pinfunction "1_1") (pintype "passive"))
      (node (ref "R208") (pin "1") (pinfunction "1_1") (pintype "passive"))
      (node (ref "U205") (pin "13") (pinfunction "A_13") (pintype "bidirectional"))
    )
    (net (code "53") (name "Net-(Q203-D)") (class "Default")
      (node (ref "Q203") (pin "3") (pinfunction "D_3") (pintype "passive"))
      (node (ref "R201") (pin "1") (pinfunction "1_1") (pintype "passive"))
      (node (ref "R202") (pin "1") (pinfunction "1_1") (pintype "passive"))
      (node (ref "R203") (pin "1") (pinfunction "1_1") (pintype "passive"))
    )
    (net (code "54") (name "Net-(Q204-D)") (class "Default")
      (node (ref "Q204") (pin "3") (pinfunction "D_3") (pintype "passive"))
      (node (ref "R204") (pin "1") (pinfunction "1_1") (pintype "passive"))
      (node (ref "R205") (pin "1") (pinfunction "1_1") (pintype "passive"))
    )
    (net (code "55") (name "Net-(Q502-G)") (class "Default")
      (node (ref "C517") (pin "1") (pinfunction "1_1") (pintype "passive"))
      (node (ref "C518") (pin "1") (pinfunction "1_1") (pintype "passive"))
      (node (ref "C519") (pin "1") (pinfunction "1_1") (pintype "passive"))
      (node (ref "D502") (pin "C") (pinfunction "C_C") (pintype "passive"))
      (node (ref "Q502") (pin "2") (pinfunction "G_2") (pintype "passive"))
      (node (ref "Q503") (pin "3") (pinfunction "D_3") (pintype "passive"))
      (node (ref "R505") (pin "1") (pinfunction "1_1") (pintype "passive"))
      (node (ref "R507") (pin "1") (pinfunction "1_1") (pintype "passive"))
      (node (ref "R509") (pin "2") (pinfunction "2_2") (pintype "passive"))
    )
    (net (code "56") (name "Net-(Q601-D)") (class "Default")
      (node (ref "Q601") (pin "3") (pinfunction "D_3") (pintype "passive"))
      (node (ref "R605") (pin "1") (pinfunction "1_1") (pintype "passive"))
    )
    (net (code "57") (name "Net-(Q601-G)") (class "Default")
      (node (ref "Q601") (pin "2") (pinfunction "G_2") (pintype "passive"))
      (node (ref "R606") (pin "2") (pinfunction "2_2") (pintype "passive"))
    )
    (net (code "58") (name "Net-(R507-Pad2)") (class "Default")
      (node (ref "R507") (pin "2") (pinfunction "2_2") (pintype "passive"))
      (node (ref "S501") (pin "2") (pinfunction "2_2") (pintype "passive"))
    )
    (net (code "59") (name "Net-(U101A-PA1)") (class "Default")
      (node (ref "R102") (pin "2") (pinfunction "2_2") (pintype "passive"))
      (node (ref "U101") (pin "11") (pinfunction "PA1_11") (pintype "bidirectional"))
    )
    (net (code "60") (name "Net-(U101A-PA2)") (class "Default")
      (node (ref "R104") (pin "2") (pinfunction "2_2") (pintype "passive"))
      (node (ref "U101") (pin "12") (pinfunction "PA2_12") (pintype "bidirectional"))
    )
    (net (code "61") (name "Net-(U101A-PA4)") (class "Default")
      (node (ref "R106") (pin "2") (pinfunction "2_2") (pintype "passive"))
      (node (ref "U101") (pin "14") (pinfunction "PA4_14") (pintype "bidirectional"))
    )
    (net (code "62") (name "Net-(U101A-PA7)") (class "Default")
      (node (ref "R110") (pin "2") (pinfunction "2_2") (pintype "passive"))
      (node (ref "U101") (pin "17") (pinfunction "PA7_17") (pintype "bidirectional"))
    )
    (net (code "63") (name "Net-(U101A-PA8)") (class "Default")
      (node (ref "R112") (pin "2") (pinfunction "2_2") (pintype "passive"))
      (node (ref "U101") (pin "29") (pinfunction "PA8_29") (pintype "bidirectional"))
    )
    (net (code "64") (name "Net-(U101A-PA12)") (class "Default")
      (node (ref "R117") (pin "2") (pinfunction "2_2") (pintype "passive"))
      (node (ref "U101") (pin "33") (pinfunction "PA12_33") (pintype "bidirectional"))
    )
    (net (code "65") (name "Net-(U101A-PA13)") (class "Default")
      (node (ref "R119") (pin "2") (pinfunction "2_2") (pintype "passive"))
      (node (ref "U101") (pin "34") (pinfunction "PA13_34") (pintype "bidirectional"))
    )
    (net (code "66") (name "Net-(U101A-PA14)") (class "Default")
      (node (ref "R121") (pin "2") (pinfunction "2_2") (pintype "passive"))
      (node (ref "U101") (pin "37") (pinfunction "PA14_37") (pintype "bidirectional"))
    )
    (net (code "67") (name "Net-(U101A-PA15)") (class "Default")
      (node (ref "R123") (pin "2") (pinfunction "2_2") (pintype "passive"))
      (node (ref "U101") (pin "38") (pinfunction "PA15_38") (pintype "bidirectional"))
    )
    (net (code "68") (name "Net-(U101B-PB1)") (class "Default")
      (node (ref "R103") (pin "2") (pinfunction "2_2") (pintype "passive"))
      (node (ref "U101") (pin "19") (pinfunction "PB1_19") (pintype "bidirectional"))
    )
    (net (code "69") (name "Net-(U101B-PB3)") (class "Default")
      (node (ref "R105") (pin "2") (pinfunction "2_2") (pintype "passive"))
      (node (ref "U101") (pin "39") (pinfunction "PB3_39") (pintype "bidirectional"))
    )
    (net (code "70") (name "Net-(U101B-PB4)") (class "Default")
      (node (ref "R107") (pin "2") (pinfunction "2_2") (pintype "passive"))
      (node (ref "U101") (pin "40") (pinfunction "PB4_40") (pintype "bidirectional"))
    )
    (net (code "71") (name "Net-(U101B-PB5)") (class "Default")
      (node (ref "R108") (pin "2") (pinfunction "2_2") (pintype "passive"))
      (node (ref "U101") (pin "41") (pinfunction "PB5_41") (pintype "bidirectional"))
    )
    (net (code "72") (name "Net-(U101B-PB6)") (class "Default")
      (node (ref "R109") (pin "2") (pinfunction "2_2") (pintype "passive"))
      (node (ref "U101") (pin "42") (pinfunction "PB6_42") (pintype "bidirectional"))
    )
    (net (code "73") (name "Net-(U101B-PB7)") (class "Default")
      (node (ref "L101") (pin "1") (pinfunction "1_1") (pintype "passive"))
      (node (ref "U101") (pin "43") (pinfunction "PB7_43") (pintype "bidirectional"))
    )
    (net (code "74") (name "Net-(U101B-PB8)") (class "Default")
      (node (ref "L102") (pin "1") (pinfunction "1_1") (pintype "passive"))
      (node (ref "U101") (pin "45") (pinfunction "PB8_45") (pintype "bidirectional"))
    )
    (net (code "75") (name "Net-(U101B-PB9)") (class "Default")
      (node (ref "R114") (pin "2") (pinfunction "2_2") (pintype "passive"))
      (node (ref "R126") (pin "1") (pinfunction "1_1") (pintype "passive"))
      (node (ref "U101") (pin "46") (pinfunction "PB9_46") (pintype "bidirectional"))
    )
    (net (code "76") (name "Net-(U101B-PB10)") (class "Default")
      (node (ref "R115") (pin "2") (pinfunction "2_2") (pintype "passive"))
      (node (ref "U101") (pin "21") (pinfunction "PB10_21") (pintype "bidirectional"))
    )
    (net (code "77") (name "Net-(U101B-PB11)") (class "Default")
      (node (ref "R116") (pin "2") (pinfunction "2_2") (pintype "passive"))
      (node (ref "U101") (pin "22") (pinfunction "PB11_22") (pintype "bidirectional"))
    )
    (net (code "78") (name "Net-(U101B-PB12)") (class "Default")
      (node (ref "R118") (pin "2") (pinfunction "2_2") (pintype "passive"))
      (node (ref "U101") (pin "25") (pinfunction "PB12_25") (pintype "bidirectional"))
    )
    (net (code "79") (name "Net-(U101B-PB13)") (class "Default")
      (node (ref "R120") (pin "2") (pinfunction "2_2") (pintype "passive"))
      (node (ref "R122") (pin "2") (pinfunction "2_2") (pintype "passive"))
      (node (ref "U101") (pin "26") (pinfunction "PB13_26") (pintype "bidirectional"))
    )
    (net (code "80") (name "Net-(U101C-NRST)") (class "Default")
      (node (ref "C112") (pin "1") (pinfunction "1_1") (pintype "passive"))
      (node (ref "R101") (pin "2") (pinfunction "2_2") (pintype "passive"))
      (node (ref "U101") (pin "7") (pinfunction "NRST_7") (pintype "bidirectional"))
    )
    (net (code "81") (name "Net-(U101C-PD0{slash}OSC_O)") (class "Default")
      (node (ref "C109") (pin "1") (pinfunction "1_1") (pintype "passive"))
      (node (ref "U101") (pin "5") (pinfunction "PD0/OSC_O_5") (pintype "bidirectional"))
      (node (ref "X101") (pin "2") (pinfunction "XIN_2") (pintype "bidirectional"))
    )
    (net (code "82") (name "Net-(U101C-PD1{slash}OSC_I)") (class "Default")
      (node (ref "C110") (pin "1") (pinfunction "1_1") (pintype "passive"))
      (node (ref "U101") (pin "6") (pinfunction "PD1/OSC_I_6") (pintype "bidirectional"))
      (node (ref "X101") (pin "3") (pinfunction "XOUT_3") (pintype "bidirectional"))
    )
    (net (code "83") (name "Net-(U101C-VBAT)") (class "Default")
      (node (ref "C111") (pin "1") (pinfunction "1_1") (pintype "passive"))
      (node (ref "U101") (pin "1") (pinfunction "VBAT_1") (pintype "bidirectional"))
    )
    (net (code "84") (name "Net-(U201B-COM)") (class "Default")
      (node (ref "R224") (pin "1") (pinfunction "1_1") (pintype "passive"))
      (node (ref "U201") (pin "10") (pinfunction "COM_10") (pintype "bidirectional"))
      (node (ref "U201") (pin "2") (pinfunction "COM_2") (pintype "bidirectional"))
      (node (ref "U201") (pin "4") (pinfunction "COM_4") (pintype "bidirectional"))
      (node (ref "U201") (pin "9") (pinfunction "COM_9") (pintype "bidirectional"))
      (node (ref "U207") (pin "7") (pinfunction "Y_7") (pintype "bidirectional"))
    )
    (net (code "85") (name "Net-(U201B-NO)") (class "Default")
      (node (ref "R208") (pin "2") (pinfunction "2_2") (pintype "passive"))
      (node (ref "U201") (pin "1") (pinfunction "NO_1") (pintype "bidirectional"))
    )
    (net (code "86") (name "Net-(U201C-NO)") (class "Default")
      (node (ref "R207") (pin "2") (pinfunction "2_2") (pintype "passive"))
      (node (ref "U201") (pin "3") (pinfunction "NO_3") (pintype "bidirectional"))
    )
    (net (code "87") (name "Net-(U202B-COM)") (class "Default")
      (node (ref "C209") (pin "2") (pinfunction "2_2") (pintype "passive"))
      (node (ref "U202") (pin "5") (pinfunction "COM_5") (pintype "bidirectional"))
    )
    (net (code "88") (name "Net-(U202B-NO)") (class "Default")
      (node (ref "C213") (pin "2") (pinfunction "2_2") (pintype "passive"))
      (node (ref "C216") (pin "2") (pinfunction "2_2") (pintype "passive"))
      (node (ref "R226") (pin "1") (pinfunction "1_1") (pintype "passive"))
      (node (ref "U202") (pin "6") (pinfunction "NO_6") (pintype "bidirectional"))
      (node (ref "U203") (pin "6") (pinfunction "NO_6") (pintype "bidirectional"))
      (node (ref "U204") (pin "6") (pinfunction "NO_6") (pintype "bidirectional"))
      (node (ref "U205") (pin "6") (pinfunction "Y_6") (pintype "bidirectional"))
    )
    (net (code "89") (name "Net-(U205A-Y)") (class "Default")
      (node (ref "R211") (pin "1") (pinfunction "1_1") (pintype "passive"))
      (node (ref "U205") (pin "2") (pinfunction "Y_2") (pintype "bidirectional"))
      (node (ref "U205") (pin "3") (pinfunction "A_3") (pintype "bidirectional"))
    )
    (net (code "90") (name "Net-(U205B-Y)") (class "Default")
      (node (ref "R215") (pin "2") (pinfunction "2_2") (pintype "passive"))
      (node (ref "U205") (pin "4") (pinfunction "Y_4") (pintype "bidirectional"))
      (node (ref "U205") (pin "5") (pinfunction "A_5") (pintype "bidirectional"))
    )
    (net (code "91") (name "Net-(U205D-A)") (class "Default")
      (node (ref "R214") (pin "1") (pinfunction "1_1") (pintype "passive"))
      (node (ref "U205") (pin "10") (pinfunction "Y_10") (pintype "bidirectional"))
      (node (ref "U205") (pin "9") (pinfunction "A_9") (pintype "bidirectional"))
    )
    (net (code "92") (name "Net-(U205D-Y)") (class "Default")
      (node (ref "C212") (pin "2") (pinfunction "2_2") (pintype "passive"))
      (node (ref "C215") (pin "2") (pinfunction "2_2") (pintype "passive"))
      (node (ref "R223") (pin "1") (pinfunction "1_1") (pintype "passive"))
      (node (ref "U205") (pin "8") (pinfunction "Y_8") (pintype "bidirectional"))
    )
    (net (code "93") (name "Net-(U205E-A)") (class "Default")
      (node (ref "R210") (pin "2") (pinfunction "2_2") (pintype "passive"))
      (node (ref "U205") (pin "11") (pinfunction "A_11") (pintype "bidirectional"))
      (node (ref "U205") (pin "12") (pinfunction "Y_12") (pintype "bidirectional"))
    )
    (net (code "94") (name "Net-(U206-SENSE1)") (class "Default")
      (node (ref "R221") (pin "1") (pinfunction "1_1") (pintype "passive"))
      (node (ref "R222") (pin "1") (pinfunction "1_1") (pintype "passive"))
      (node (ref "U206") (pin "4") (pinfunction "SENSE1_4") (pintype "bidirectional"))
    )
    (net (code "95") (name "Net-(U206-SENSE2)") (class "Default")
      (node (ref "R216") (pin "1") (pinfunction "1_1") (pintype "passive"))
      (node (ref "R217") (pin "1") (pinfunction "1_1") (pintype "passive"))
      (node (ref "R218") (pin "1") (pinfunction "1_1") (pintype "passive"))
      (node (ref "R221") (pin "2") (pinfunction "2_2") (pintype "passive"))
      (node (ref "R222") (pin "2") (pinfunction "2_2") (pintype "passive"))
      (node (ref "U206") (pin "5") (pinfunction "SENSE2_5") (pintype "bidirectional"))
    )
    (net (code "96") (name "Net-(U207A-A)") (class "Default")
      (node (ref "R219") (pin "2") (pinfunction "2_2") (pintype "passive"))
      (node (ref "U207") (pin "1") (pinfunction "A_1") (pintype "bidirectional"))
      (node (ref "U207") (pin "5") (pinfunction "Y_5") (pintype "bidirectional"))
    )
    (net (code "97") (name "Net-(U207B-A)") (class "Default")
      (node (ref "C218") (pin "1") (pinfunction "1_1") (pintype "passive"))
      (node (ref "R219") (pin "1") (pinfunction "1_1") (pintype "passive"))
      (node (ref "R223") (pin "2") (pinfunction "2_2") (pintype "passive"))
      (node (ref "U207") (pin "3") (pinfunction "A_3") (pintype "bidirectional"))
    )
    (net (code "98") (name "Net-(U207C-A)") (class "Default")
      (node (ref "C219") (pin "1") (pinfunction "1_1") (pintype "passive"))
      (node (ref "R220") (pin "1") (pinfunction "1_1") (pintype "passive"))
      (node (ref "R226") (pin "2") (pinfunction "2_2") (pintype "passive"))
      (node (ref "U207") (pin "6") (pinfunction "A_6") (pintype "bidirectional"))
    )
    (net (code "99") (name "Net-(U207C-Y)") (class "Default")
      (node (ref "R212") (pin "1") (pinfunction "1_1") (pintype "passive"))
      (node (ref "R220") (pin "2") (pinfunction "2_2") (pintype "passive"))
      (node (ref "R225") (pin "1") (pinfunction "1_1") (pintype "passive"))
      (node (ref "U207") (pin "2") (pinfunction "Y_2") (pintype "bidirectional"))
    )
    (net (code "100") (name "Net-(U208A-A)") (class "Default")
      (node (ref "R225") (pin "2") (pinfunction "2_2") (pintype "passive"))
      (node (ref "U208") (pin "1") (pinfunction "A_1") (pintype "bidirectional"))
    )
    (net (code "101") (name "Net-(U208A-C)") (class "Default")
      (node (ref "R224") (pin "2") (pinfunction "2_2") (pintype "passive"))
      (node (ref "U208") (pin "6") (pinfunction "C_6") (pintype "bidirectional"))
    )
    (net (code "102") (name "Net-(U301-IN)") (class "Default")
      (node (ref "C308") (pin "2") (pinfunction "2_2") (pintype "passive"))
      (node (ref "U301") (pin "3") (pinfunction "IN_3") (pintype "bidirectional"))
    )
    (net (code "103") (name "Net-(U301-OUTN)") (class "Default")
      (node (ref "U301") (pin "4") (pinfunction "OUTN_4") (pintype "bidirectional"))
      (node (ref "U302") (pin "5") (pinfunction "MIX_IN_N_5") (pintype "bidirectional"))
    )
    (net (code "104") (name "Net-(U301-OUTP)") (class "Default")
      (node (ref "U301") (pin "5") (pinfunction "OUTP_5") (pintype "bidirectional"))
      (node (ref "U302") (pin "4") (pinfunction "MIX_IN_P_4") (pintype "bidirectional"))
    )
    (net (code "105") (name "Net-(U302-IBIAS)") (class "Default")
      (node (ref "R303") (pin "1") (pinfunction "1_1") (pintype "passive"))
      (node (ref "U302") (pin "1") (pinfunction "IBIAS_1") (pintype "bidirectional"))
    )
    (net (code "106") (name "Net-(U302-LDO2_OUT)") (class "Default")
      (node (ref "C304") (pin "2") (pinfunction "2_2") (pintype "passive"))
      (node (ref "U302") (pin "53") (pinfunction "LDO2_OUT_53") (pintype "bidirectional"))
    )
    (net (code "107") (name "Net-(U302-PIO4{slash}RXD1)") (class "Default")
      (node (ref "C318") (pin "2") (pinfunction "2_2") (pintype "passive"))
      (node (ref "R307") (pin "1") (pinfunction "1_1") (pintype "passive"))
      (node (ref "U302") (pin "24") (pinfunction "PIO4/RXD1_24") (pintype "bidirectional"))
    )
    (net (code "108") (name "Net-(U302-PIO5{slash}TXD1)") (class "Default")
      (node (ref "C317") (pin "2") (pinfunction "2_2") (pintype "passive"))
      (node (ref "R306") (pin "1") (pinfunction "1_1") (pintype "passive"))
      (node (ref "U302") (pin "21") (pinfunction "PIO5/TXD1_21") (pintype "bidirectional"))
    )
    (net (code "109") (name "Net-(U302-VDCTEST)") (class "Default")
      (node (ref "C307") (pin "1") (pinfunction "1_1") (pintype "passive"))
      (node (ref "U302") (pin "3") (pinfunction "VDCTEST_3") (pintype "bidirectional"))
    )
    (net (code "110") (name "Net-(U302-VDD_3V)") (class "Default")
      (node (ref "C301") (pin "1") (pinfunction "1_1") (pintype "passive"))
      (node (ref "C306") (pin "1") (pinfunction "1_1") (pintype "passive"))
      (node (ref "L301") (pin "2") (pinfunction "2_2") (pintype "passive"))
      (node (ref "L305") (pin "2") (pinfunction "2_2") (pintype "passive"))
      (node (ref "U302") (pin "50") (pinfunction "VDD_3V_50") (pintype "bidirectional"))
    )
    (net (code "111") (name "Net-(U302-VDD_B)") (class "Default")
      (node (ref "C313") (pin "2") (pinfunction "2_2") (pintype "passive"))
      (node (ref "U302") (pin "30") (pinfunction "VDD_B_30") (pintype "bidirectional"))
    )
    (net (code "112") (name "Net-(U302-VDD_C0)") (class "Default")
      (node (ref "C314") (pin "2") (pinfunction "2_2") (pintype "passive"))
      (node (ref "R305") (pin "2") (pinfunction "2_2") (pintype "passive"))
      (node (ref "U302") (pin "17") (pinfunction "VDD_C0_17") (pintype "bidirectional"))
    )
    (net (code "113") (name "Net-(U302-VDD_C1)") (class "Default")
      (node (ref "C312") (pin "2") (pinfunction "2_2") (pintype "passive"))
      (node (ref "U302") (pin "31") (pinfunction "VDD_C1_31") (pintype "bidirectional"))
    )
    (net (code "114") (name "Net-(U302-VDD_LNA)") (class "Default")
      (node (ref "C303") (pin "2") (pinfunction "2_2") (pintype "passive"))
      (node (ref "U302") (pin "55") (pinfunction "VDD_LNA_55") (pintype "bidirectional"))
    )
    (net (code "115") (name "Net-(U302-VDD_PLL)") (class "Default")
      (node (ref "C311") (pin "1") (pinfunction "1_1") (pintype "passive"))
      (node (ref "R305") (pin "1") (pinfunction "1_1") (pintype "passive"))
      (node (ref "U302") (pin "9") (pinfunction "VDD_PLL_9") (pintype "bidirectional"))
    )
    (net (code "116") (name "Net-(U302-VDD_RF)") (class "Default")
      (node (ref "C305") (pin "2") (pinfunction "2_2") (pintype "passive"))
      (node (ref "U302") (pin "51") (pinfunction "VDD_RF_51") (pintype "bidirectional"))
    )
    (net (code "117") (name "Net-(U302-VSS_PLL)") (class "Default")
      (node (ref "C311") (pin "2") (pinfunction "2_2") (pintype "passive"))
      (node (ref "U302") (pin "8") (pinfunction "VSS_PLL_8") (pintype "bidirectional"))
    )
    (net (code "118") (name "Net-(U303-IN)") (class "Default")
      (node (ref "L304") (pin "2") (pinfunction "2_2") (pintype "passive"))
      (node (ref "R304") (pin "1") (pinfunction "1_1") (pintype "passive"))
      (node (ref "U303") (pin "4") (pinfunction "IN_4") (pintype "bidirectional"))
    )
    (net (code "119") (name "Net-(U303-OUT)") (class "Default")
      (node (ref "L302") (pin "1") (pinfunction "1_1") (pintype "passive"))
      (node (ref "U303") (pin "5") (pinfunction "OUT_5") (pintype "bidirectional"))
    )
    (net (code "120") (name "Net-(U304-IN)") (class "Default")
      (node (ref "L302") (pin "2") (pinfunction "2_2") (pintype "passive"))
      (node (ref "U304") (pin "6") (pinfunction "IN_6") (pintype "bidirectional"))
    )
    (net (code "121") (name "Net-(U304-OUT)") (class "Default")
      (node (ref "L303") (pin "1") (pinfunction "1_1") (pintype "passive"))
      (node (ref "U304") (pin "3") (pinfunction "OUT_3") (pintype "bidirectional"))
    )
    (net (code "122") (name "Net-(U401-GPIO_1)") (class "Default")
      (node (ref "R406") (pin "1") (pinfunction "1_1") (pintype "passive"))
      (node (ref "U401") (pin "8") (pinfunction "GPIO_1_8") (pintype "bidirectional"))
    )
    (net (code "123") (name "Net-(U401-GPIO_2)") (class "Default")
      (node (ref "R403") (pin "1") (pinfunction "1_1") (pintype "passive"))
      (node (ref "U401") (pin "9") (pinfunction "GPIO_2_9") (pintype "bidirectional"))
    )
    (net (code "124") (name "Net-(U401-TX)") (class "Default")
      (node (ref "C404") (pin "2") (pinfunction "2_2") (pintype "passive"))
      (node (ref "L408") (pin "2") (pinfunction "2_2") (pintype "passive"))
      (node (ref "U401") (pin "2") (pinfunction "TX_2") (pintype "bidirectional"))
    )
    (net (code "125") (name "Net-(U401-VDD_DIG)") (class "Default")
      (node (ref "C410") (pin "1") (pinfunction "1_1") (pintype "passive"))
      (node (ref "C411") (pin "1") (pinfunction "1_1") (pintype "passive"))
      (node (ref "L410") (pin "1") (pinfunction "1_1") (pintype "passive"))
      (node (ref "U401") (pin "12") (pinfunction "VDD_DIG_12") (pintype "bidirectional"))
    )
    (net (code "126") (name "Net-(U401-VDD_RF)") (class "Default")
      (node (ref "C414") (pin "1") (pinfunction "1_1") (pintype "passive"))
      (node (ref "C415") (pin "1") (pinfunction "1_1") (pintype "passive"))
      (node (ref "C416") (pin "1") (pinfunction "1_1") (pintype "passive"))
      (node (ref "C417") (pin "1") (pinfunction "1_1") (pintype "passive"))
      (node (ref "L409") (pin "2") (pinfunction "2_2") (pintype "passive"))
      (node (ref "R405") (pin "2") (pinfunction "2_2") (pintype "passive"))
      (node (ref "U401") (pin "1") (pinfunction "VDD_RF_1") (pintype "bidirectional"))
    )
    (net (code "127") (name "Net-(U401-VDR)") (class "Default")
      (node (ref "C420") (pin "1") (pinfunction "1_1") (pintype "passive"))
      (node (ref "C421") (pin "1") (pinfunction "1_1") (pintype "passive"))
      (node (ref "U401") (pin "10") (pinfunction "VDR_10") (pintype "bidirectional"))
    )
    (net (code "128") (name "Net-(U401-XOUT)") (class "Default")
      (node (ref "C401") (pin "1") (pinfunction "1_1") (pintype "passive"))
      (node (ref "U401") (pin "18") (pinfunction "XOUT_18") (pintype "bidirectional"))
    )
    (net (code "129") (name "Net-(U501-NC)") (class "Default")
      (node (ref "C506") (pin "1") (pinfunction "1_1") (pintype "passive"))
      (node (ref "U501") (pin "4") (pinfunction "NC_4") (pintype "bidirectional"))
    )
    (net (code "130") (name "Net-(U502-FB)") (class "Default")
      (node (ref "R503") (pin "1") (pinfunction "1_1") (pintype "passive"))
      (node (ref "R504") (pin "2") (pinfunction "2_2") (pintype "passive"))
      (node (ref "U502") (pin "10") (pinfunction "FB_10") (pintype "bidirectional"))
    )
    (net (code "131") (name "Net-(U502-L)") (class "Default")
      (node (ref "L501") (pin "2") (pinfunction "2_2") (pintype "passive"))
      (node (ref "U502") (pin "3") (pinfunction "L_3") (pintype "bidirectional"))
    )
    (net (code "132") (name "Net-(U502-VAUX)") (class "Default")
      (node (ref "C510") (pin "1") (pinfunction "1_1") (pintype "passive"))
      (node (ref "U502") (pin "1") (pinfunction "VAUX_1") (pintype "bidirectional"))
    )
    (net (code "133") (name "Net-(U503-NC)") (class "Default")
      (node (ref "C516") (pin "1") (pinfunction "1_1") (pintype "passive"))
      (node (ref "U503") (pin "4") (pinfunction "NC_4") (pintype "bidirectional"))
    )
    (net (code "134") (name "Net-(U504-NC)") (class "Default")
      (node (ref "C526") (pin "1") (pinfunction "1_1") (pintype "passive"))
      (node (ref "U504") (pin "4") (pinfunction "NC_4") (pintype "bidirectional"))
    )
    (net (code "135") (name "PULLUP_HYG") (class "Default")
      (node (ref "C113") (pin "1") (pinfunction "1_1") (pintype "passive"))
      (node (ref "Q202") (pin "1") (pinfunction "G_1") (pintype "passive"))
      (node (ref "R104") (pin "1") (pinfunction "1_1") (pintype "passive"))
    )
    (net (code "136") (name "PULLUP_TMP") (class "Default")
      (node (ref "C124") (pin "2") (pinfunction "2_2") (pintype "passive"))
      (node (ref "Q201") (pin "1") (pinfunction "G_1") (pintype "passive"))
      (node (ref "R118") (pin "1") (pinfunction "1_1") (pintype "passive"))
    )
    (net (code "137") (name "RADIO_ANT_PRI") (class "Default")
      (node (ref "C405") (pin "1") (pinfunction "1_1") (pintype "passive"))
      (node (ref "C409") (pin "2") (pinfunction "2_2") (pintype "passive"))
      (node (ref "L402") (pin "1") (pinfunction "1_1") (pintype "passive"))
      (node (ref "L406") (pin "2") (pinfunction "2_2") (pintype "passive"))
    )
    (net (code "138") (name "RADIO_CLK") (class "Default")
      (node (ref "C401") (pin "2") (pinfunction "2_2") (pintype "passive"))
      (node (ref "R309") (pin "1") (pinfunction "1_1") (pintype "passive"))
    )
    (net (code "139") (name "RADIO_PROBE_POINT") (class "Default")
      (node (ref "R403") (pin "2") (pinfunction "2_2") (pintype "passive"))
      (node (ref "TP1") (pin "TP") (pinfunction "TP_TP") (pintype "input"))
    )
    (net (code "140") (name "REF_R_THERM") (class "Default")
      (node (ref "C116") (pin "2") (pinfunction "2_2") (pintype "passive"))
      (node (ref "R103") (pin "1") (pinfunction "1_1") (pintype "passive"))
      (node (ref "R125") (pin "1") (pinfunction "1_1") (pintype "passive"))
      (node (ref "R209") (pin "1") (pinfunction "1_1") (pintype "passive"))
    )
    (net (code "141") (name "RPM_CLOCK") (class "Default")
      (node (ref "R112") (pin "1") (pinfunction "1_1") (pintype "passive"))
    )
    (net (code "142") (name "SHUTDOWN") (class "Default")
      (node (ref "C522") (pin "1") (pinfunction "1_1") (pintype "passive"))
      (node (ref "Q503") (pin "2") (pinfunction "G_2") (pintype "passive"))
      (node (ref "R117") (pin "1") (pinfunction "1_1") (pintype "passive"))
      (node (ref "R511") (pin "1") (pinfunction "1_1") (pintype "passive"))
    )
    (net (code "143") (name "SPDT1") (class "Default")
      (node (ref "C117") (pin "2") (pinfunction "2_2") (pintype "passive"))
      (node (ref "R105") (pin "1") (pinfunction "1_1") (pintype "passive"))
      (node (ref "U202") (pin "1") (pinfunction "IN_1") (pintype "bidirectional"))
    )
    (net (code "144") (name "SPDT2") (class "Default")
      (node (ref "C118") (pin "2") (pinfunction "2_2") (pintype "passive"))
      (node (ref "R107") (pin "1") (pinfunction "1_1") (pintype "passive"))
      (node (ref "U203") (pin "1") (pinfunction "IN_1") (pintype "bidirectional"))
    )
    (net (code "145") (name "SPDT3") (class "Default")
      (node (ref "C119") (pin "2") (pinfunction "2_2") (pintype "passive"))
      (node (ref "R108") (pin "1") (pinfunction "1_1") (pintype "passive"))
      (node (ref "U204") (pin "1") (pinfunction "IN_1") (pintype "bidirectional"))
    )
    (net (code "146") (name "SPI_CS") (class "Default")
      (node (ref "J601") (pin "10") (pinfunction "12_10") (pintype "passive"))
      (node (ref "U101") (pin "20") (pinfunction "PB2_20") (pintype "bidirectional"))
      (node (ref "U601") (pin "1") (pinfunction "~{CS}_1") (pintype "input"))
    )
    (net (code "147") (name "SPI_SCK") (class "Default")
      (node (ref "J601") (pin "4") (pinfunction "15_4") (pintype "passive"))
      (node (ref "R120") (pin "1") (pinfunction "1_1") (pintype "passive"))
      (node (ref "U601") (pin "6") (pinfunction "SCK_6") (pintype "input"))
    )
    (net (code "148") (name "SPI_SCK_RADIO") (class "Default")
      (node (ref "R122") (pin "1") (pinfunction "1_1") (pintype "passive"))
      (node (ref "U401") (pin "15") (pinfunction "SCLK_15") (pintype "bidirectional"))
    )
    (net (code "149") (name "SPI_SDI") (class "Default")
      (node (ref "J601") (pin "6") (pinfunction "14_6") (pintype "passive"))
      (node (ref "U101") (pin "27") (pinfunction "PB14_27") (pintype "bidirectional"))
      (node (ref "U401") (pin "13") (pinfunction "SDO_13") (pintype "bidirectional"))
      (node (ref "U601") (pin "2") (pinfunction "SO_2") (pintype "bidirectional"))
    )
    (net (code "150") (name "SPI_SDO") (class "Default")
      (node (ref "J601") (pin "8") (pinfunction "13_8") (pintype "passive"))
      (node (ref "U101") (pin "28") (pinfunction "PB15_28") (pintype "bidirectional"))
      (node (ref "U401") (pin "14") (pinfunction "SDI_14") (pintype "bidirectional"))
      (node (ref "U601") (pin "5") (pinfunction "SI_5") (pintype "input"))
    )
    (net (code "151") (name "SPST1") (class "Default")
      (node (ref "C120") (pin "2") (pinfunction "2_2") (pintype "passive"))
      (node (ref "R109") (pin "1") (pinfunction "1_1") (pintype "passive"))
      (node (ref "U201") (pin "13") (pinfunction "IN_13") (pintype "bidirectional"))
    )
    (net (code "152") (name "SPST2") (class "Default")
      (node (ref "U101") (pin "13") (pinfunction "PA3_13") (pintype "bidirectional"))
      (node (ref "U201") (pin "5") (pinfunction "IN_5") (pintype "bidirectional"))
    )
    (net (code "153") (name "SPST3") (class "Default")
      (node (ref "U101") (pin "3") (pinfunction "PC14_3") (pintype "bidirectional"))
      (node (ref "U201") (pin "6") (pinfunction "IN_6") (pintype "bidirectional"))
    )
    (net (code "154") (name "SPST4") (class "Default")
      (node (ref "U101") (pin "4") (pinfunction "PC15_4") (pintype "bidirectional"))
      (node (ref "U201") (pin "12") (pinfunction "IN_12") (pintype "bidirectional"))
    )
    (net (code "155") (name "SW") (class "Default")
      (node (ref "C524") (pin "1") (pinfunction "1_1") (pintype "passive"))
      (node (ref "R509") (pin "1") (pinfunction "1_1") (pintype "passive"))
      (node (ref "R513") (pin "2") (pinfunction "2_2") (pintype "passive"))
      (node (ref "U101") (pin "16") (pinfunction "PA6_16") (pintype "bidirectional"))
    )
    (net (code "156") (name "VBAT") (class "Default")
      (node (ref "C504") (pin "2") (pinfunction "2_2") (pintype "passive"))
      (node (ref "C505") (pin "2") (pinfunction "2_2") (pintype "passive"))
      (node (ref "C511") (pin "1") (pinfunction "1_1") (pintype "passive"))
      (node (ref "D501") (pin "C") (pinfunction "C_C") (pintype "passive"))
      (node (ref "F501") (pin "2") (pinfunction "2_2") (pintype "passive"))
      (node (ref "J602") (pin "6") (pinfunction "8_6") (pintype "passive"))
      (node (ref "Q501") (pin "2") (pinfunction "S_2") (pintype "passive"))
      (node (ref "R501") (pin "1") (pinfunction "1_1") (pintype "passive"))
      (node (ref "S501") (pin "1") (pinfunction "1_1") (pintype "passive"))
    )
    (net (code "157") (name "VBAT_MON") (class "Default")
      (node (ref "C523") (pin "1") (pinfunction "1_1") (pintype "passive"))
      (node (ref "R508") (pin "1") (pinfunction "1_1") (pintype "passive"))
      (node (ref "R512") (pin "2") (pinfunction "2_2") (pintype "passive"))
      (node (ref "U101") (pin "15") (pinfunction "PA5_15") (pintype "bidirectional"))
    )
    (net (code "158") (name "VBAT_SW") (class "Default")
      (node (ref "C512") (pin "1") (pinfunction "1_1") (pintype "passive"))
      (node (ref "L501") (pin "1") (pinfunction "1_1") (pintype "passive"))
      (node (ref "Q501") (pin "3") (pinfunction "D_3") (pintype "passive"))
      (node (ref "R505") (pin "2") (pinfunction "2_2") (pintype "passive"))
      (node (ref "R508") (pin "2") (pinfunction "2_2") (pintype "passive"))
      (node (ref "U502") (pin "5") (pinfunction "VIN_5") (pintype "bidirectional"))
      (node (ref "U502") (pin "6") (pinfunction "EN_6") (pintype "bidirectional"))
      (node (ref "U502") (pin "7") (pinfunction "UVLO_7") (pintype "bidirectional"))
      (node (ref "U502") (pin "8") (pinfunction "PS_8") (pintype "bidirectional"))
    )
    (net (code "159") (name "V_BOOST") (class "Default")
      (node (ref "C214") (pin "1") (pinfunction "1_1") (pintype "passive"))
      (node (ref "C501") (pin "1") (pinfunction "1_1") (pintype "passive"))
      (node (ref "C507") (pin "1") (pinfunction "1_1") (pintype "passive"))
      (node (ref "C508") (pin "1") (pinfunction "1_1") (pintype "passive"))
      (node (ref "C509") (pin "1") (pinfunction "1_1") (pintype "passive"))
      (node (ref "C513") (pin "1") (pinfunction "1_1") (pintype "passive"))
      (node (ref "C520") (pin "1") (pinfunction "1_1") (pintype "passive"))
      (node (ref "J201") (pin "9") (pinfunction "2_9") (pintype "passive"))
      (node (ref "J601") (pin "15") (pinfunction "8_15") (pintype "passive"))
      (node (ref "J602") (pin "5") (pinfunction "3_5") (pintype "passive"))
      (node (ref "R503") (pin "2") (pinfunction "2_2") (pintype "passive"))
      (node (ref "U501") (pin "1") (pinfunction "IN_1") (pintype "bidirectional"))
      (node (ref "U501") (pin "3") (pinfunction "EN_3") (pintype "bidirectional"))
      (node (ref "U502") (pin "2") (pinfunction "VOUT_2") (pintype "bidirectional"))
      (node (ref "U503") (pin "1") (pinfunction "IN_1") (pintype "bidirectional"))
      (node (ref "U503") (pin "3") (pinfunction "EN_3") (pintype "bidirectional"))
      (node (ref "U504") (pin "1") (pinfunction "IN_1") (pintype "bidirectional"))
      (node (ref "U504") (pin "3") (pinfunction "EN_3") (pintype "bidirectional"))
    )
    (net (code "160") (name "XDATA_RX") (class "Default")
      (node (ref "C606") (pin "2") (pinfunction "2_2") (pintype "passive"))
      (node (ref "J602") (pin "2") (pinfunction "10_2") (pintype "passive"))
      (node (ref "R116") (pin "1") (pinfunction "1_1") (pintype "passive"))
    )
    (net (code "161") (name "XDATA_SWCLK") (class "Default")
      (node (ref "D605") (pin "C") (pinfunction "C_C") (pintype "passive"))
      (node (ref "J602") (pin "8") (pinfunction "7_8") (pintype "passive"))
      (node (ref "R121") (pin "1") (pinfunction "1_1") (pintype "passive"))
    )
    (net (code "162") (name "XDATA_SWDIO") (class "Default")
      (node (ref "D606") (pin "C") (pinfunction "C_C") (pintype "passive"))
      (node (ref "J602") (pin "9") (pinfunction "5_9") (pintype "passive"))
      (node (ref "R119") (pin "1") (pinfunction "1_1") (pintype "passive"))
    )
    (net (code "163") (name "XDATA_TX") (class "Default")
      (node (ref "C607") (pin "2") (pinfunction "2_2") (pintype "passive"))
      (node (ref "J602") (pin "3") (pinfunction "2_3") (pintype "passive"))
      (node (ref "R115") (pin "1") (pinfunction "1_1") (pintype "passive"))
    )
    (net (code "164") (name "unconnected-(G501-+-Pad+@1)") (class "Default")
      (node (ref "G501") (pin "+@1") (pinfunction "+_+@1") (pintype "passive"))
    )
    (net (code "165") (name "unconnected-(J601-2-Pad3)") (class "Default")
      (node (ref "J601") (pin "3") (pinfunction "2_3") (pintype "passive"))
    )
    (net (code "166") (name "unconnected-(J601-3-Pad5)") (class "Default")
      (node (ref "J601") (pin "5") (pinfunction "3_5") (pintype "passive"))
    )
    (net (code "167") (name "unconnected-(J601-4-Pad7)") (class "Default")
      (node (ref "J601") (pin "7") (pinfunction "4_7") (pintype "passive"))
    )
    (net (code "168") (name "unconnected-(J601-5-Pad9)") (class "Default")
      (node (ref "J601") (pin "9") (pinfunction "5_9") (pintype "passive"))
    )
    (net (code "169") (name "unconnected-(J601-6-Pad11)") (class "Default")
      (node (ref "J601") (pin "11") (pinfunction "6_11") (pintype "passive"))
    )
    (net (code "170") (name "unconnected-(J601-7-Pad13)") (class "Default")
      (node (ref "J601") (pin "13") (pinfunction "7_13") (pintype "passive"))
    )
    (net (code "171") (name "unconnected-(U101C-BOOT0-Pad44)") (class "Default")
      (node (ref "U101") (pin "44") (pinfunction "BOOT0_44") (pintype "bidirectional"))
    )
    (net (code "172") (name "unconnected-(U204B-COM-Pad5)") (class "Default")
      (node (ref "U204") (pin "5") (pinfunction "COM_5") (pintype "bidirectional"))
    )
    (net (code "173") (name "unconnected-(U208B-GND-Pad2)") (class "Default")
      (node (ref "U208") (pin "2") (pinfunction "GND_2") (pintype "bidirectional"))
    )
    (net (code "174") (name "unconnected-(U208B-VCC-Pad5)") (class "Default")
      (node (ref "U208") (pin "5") (pinfunction "VCC_5") (pintype "bidirectional"))
    )
    (net (code "175") (name "unconnected-(U302-CFG_PIN{slash}TMS-Pad43)") (class "Default")
      (node (ref "U302") (pin "43") (pinfunction "CFG_PIN/TMS_43") (pintype "bidirectional"))
    )
    (net (code "176") (name "unconnected-(U302-DCDC_EN-Pad26)") (class "Default")
      (node (ref "U302") (pin "26") (pinfunction "DCDC_EN_26") (pintype "bidirectional"))
    )
    (net (code "177") (name "unconnected-(U302-EP-Pad57)") (class "Default")
      (node (ref "U302") (pin "57") (pinfunction "EP_57") (pintype "bidirectional"))
    )
    (net (code "178") (name "unconnected-(U302-LNAIN-Pad56)") (class "Default")
      (node (ref "U302") (pin "56") (pinfunction "LNAIN_56") (pintype "bidirectional"))
    )
    (net (code "179") (name "unconnected-(U302-LNAOUT-Pad2)") (class "Default")
      (node (ref "U302") (pin "2") (pinfunction "LNAOUT_2") (pintype "bidirectional"))
    )
    (net (code "180") (name "unconnected-(U302-NC1-Pad27)") (class "Default")
      (node (ref "U302") (pin "27") (pinfunction "NC1_27") (pintype "bidirectional"))
    )
    (net (code "181") (name "unconnected-(U302-NC2-Pad46)") (class "Default")
      (node (ref "U302") (pin "46") (pinfunction "NC2_46") (pintype "bidirectional"))
    )
    (net (code "182") (name "unconnected-(U302-PIO2-Pad33)") (class "Default")
      (node (ref "U302") (pin "33") (pinfunction "PIO2_33") (pintype "bidirectional"))
    )
    (net (code "183") (name "unconnected-(U302-PIO3-Pad34)") (class "Default")
      (node (ref "U302") (pin "34") (pinfunction "PIO3_34") (pintype "bidirectional"))
    )
    (net (code "184") (name "unconnected-(U302-PIO6-Pad20)") (class "Default")
      (node (ref "U302") (pin "20") (pinfunction "PIO6_20") (pintype "bidirectional"))
    )
    (net (code "185") (name "unconnected-(U302-PIO7{slash}EXTINT0-Pad44)") (class "Default")
      (node (ref "U302") (pin "44") (pinfunction "PIO7/EXTINT0_44") (pintype "bidirectional"))
    )
    (net (code "186") (name "unconnected-(U302-PIO8{slash}EXTINT1-Pad45)") (class "Default")
      (node (ref "U302") (pin "45") (pinfunction "PIO8/EXTINT1_45") (pintype "bidirectional"))
    )
    (net (code "187") (name "unconnected-(U302-PIO13{slash}CFG_CLK0-Pad41)") (class "Default")
      (node (ref "U302") (pin "41") (pinfunction "PIO13/CFG_CLK0_41") (pintype "bidirectional"))
    )
    (net (code "188") (name "unconnected-(U302-PIO14{slash}CFG_CLK1-Pad35)") (class "Default")
      (node (ref "U302") (pin "35") (pinfunction "PIO14/CFG_CLK1_35") (pintype "bidirectional"))
    )
    (net (code "189") (name "unconnected-(U302-PIO15{slash}CFG_CLK2-Pad36)") (class "Default")
      (node (ref "U302") (pin "36") (pinfunction "PIO15/CFG_CLK2_36") (pintype "bidirectional"))
    )
    (net (code "190") (name "unconnected-(U302-PIO17{slash}CFG_FFU2-Pad37)") (class "Default")
      (node (ref "U302") (pin "37") (pinfunction "PIO17/CFG_FFU2_37") (pintype "bidirectional"))
    )
    (net (code "191") (name "unconnected-(U302-PIO18{slash}CFG_FFU3-Pad16)") (class "Default")
      (node (ref "U302") (pin "16") (pinfunction "PIO18/CFG_FFU3_16") (pintype "bidirectional"))
    )
    (net (code "192") (name "unconnected-(U302-PIO19{slash}CFG_COM0-Pad32)") (class "Default")
      (node (ref "U302") (pin "32") (pinfunction "PIO19/CFG_COM0_32") (pintype "bidirectional"))
    )
    (net (code "193") (name "unconnected-(U302-PIO20{slash}CFG_COM1-Pad18)") (class "Default")
      (node (ref "U302") (pin "18") (pinfunction "PIO20/CFG_COM1_18") (pintype "bidirectional"))
    )
    (net (code "194") (name "unconnected-(U302-PIO21{slash}CFG_GPS0-Pad19)") (class "Default")
      (node (ref "U302") (pin "19") (pinfunction "PIO21/CFG_GPS0_19") (pintype "bidirectional"))
    )
    (net (code "195") (name "unconnected-(U302-PIO22{slash}CFG_GPS1-Pad11)") (class "Default")
      (node (ref "U302") (pin "11") (pinfunction "PIO22/CFG_GPS1_11") (pintype "bidirectional"))
    )
    (net (code "196") (name "unconnected-(U302-PIO23{slash}CFG_GPS2-Pad10)") (class "Default")
      (node (ref "U302") (pin "10") (pinfunction "PIO23/CFG_GPS2_10") (pintype "bidirectional"))
    )
    (net (code "197") (name "unconnected-(U302-RTC_XTAL_I-Pad7)") (class "Default")
      (node (ref "U302") (pin "7") (pinfunction "RTC_XTAL_I_7") (pintype "bidirectional"))
    )
    (net (code "198") (name "unconnected-(U302-RTC_XTAL_O-Pad6)") (class "Default")
      (node (ref "U302") (pin "6") (pinfunction "RTC_XTAL_O_6") (pintype "bidirectional"))
    )
    (net (code "199") (name "unconnected-(U302-SAFEBOOT_N{slash}TDI-Pad38)") (class "Default")
      (node (ref "U302") (pin "38") (pinfunction "SAFEBOOT_N/TDI_38") (pintype "bidirectional"))
    )
    (net (code "200") (name "unconnected-(U302-TCK-Pad40)") (class "Default")
      (node (ref "U302") (pin "40") (pinfunction "TCK_40") (pintype "bidirectional"))
    )
    (net (code "201") (name "unconnected-(U302-TCXO_POWER-Pad47)") (class "Default")
      (node (ref "U302") (pin "47") (pinfunction "TCXO_POWER_47") (pintype "bidirectional"))
    )
    (net (code "202") (name "unconnected-(U302-TDO-Pad39)") (class "Default")
      (node (ref "U302") (pin "39") (pinfunction "TDO_39") (pintype "bidirectional"))
    )
    (net (code "203") (name "unconnected-(U302-USB_DM-Pad14)") (class "Default")
      (node (ref "U302") (pin "14") (pinfunction "USB_DM_14") (pintype "bidirectional"))
    )
    (net (code "204") (name "unconnected-(U302-USB_DP-Pad13)") (class "Default")
      (node (ref "U302") (pin "13") (pinfunction "USB_DP_13") (pintype "bidirectional"))
    )
    (net (code "205") (name "unconnected-(U302-VDD_ANA-Pad54)") (class "Default")
      (node (ref "U302") (pin "54") (pinfunction "VDD_ANA_54") (pintype "bidirectional"))
    )
    (net (code "206") (name "unconnected-(U302-VDD_SYNTH-Pad52)") (class "Default")
      (node (ref "U302") (pin "52") (pinfunction "VDD_SYNTH_52") (pintype "bidirectional"))
    )
    (net (code "207") (name "unconnected-(U302-V_BCKP-Pad28)") (class "Default")
      (node (ref "U302") (pin "28") (pinfunction "V_BCKP_28") (pintype "bidirectional"))
    )
    (net (code "208") (name "unconnected-(U302-V_TH-Pad22)") (class "Default")
      (node (ref "U302") (pin "22") (pinfunction "V_TH_22") (pintype "bidirectional"))
    )
    (net (code "209") (name "unconnected-(U302-XTAL_O-Pad48)") (class "Default")
      (node (ref "U302") (pin "48") (pinfunction "XTAL_O_48") (pintype "bidirectional"))
    )
    (net (code "210") (name "unconnected-(U401-GPIO_0-Pad7)") (class "Default")
      (node (ref "U401") (pin "7") (pinfunction "GPIO_0_7") (pintype "bidirectional"))
    )
    (net (code "211") (name "unconnected-(U401-NC1-Pad3)") (class "Default")
      (node (ref "U401") (pin "3") (pinfunction "NC1_3") (pintype "bidirectional"))
    )
    (net (code "212") (name "unconnected-(U401-NC2-Pad4)") (class "Default")
      (node (ref "U401") (pin "4") (pinfunction "NC2_4") (pintype "bidirectional"))
    )
    (net (code "213") (name "unconnected-(U401-NC3-Pad5)") (class "Default")
      (node (ref "U401") (pin "5") (pinfunction "NC3_5") (pintype "bidirectional"))
    )
    (net (code "214") (name "unconnected-(U401-NC4-Pad6)") (class "Default")
      (node (ref "U401") (pin "6") (pinfunction "NC4_6") (pintype "bidirectional"))
    )
    (net (code "215") (name "unconnected-(U401-NC5-Pad11)") (class "Default")
      (node (ref "U401") (pin "11") (pinfunction "NC5_11") (pintype "bidirectional"))
    )
    (net (code "216") (name "unconnected-(U401-NIRQ-Pad17)") (class "Default")
      (node (ref "U401") (pin "17") (pinfunction "NIRQ_17") (pintype "bidirectional"))
    )
    (net (code "217") (name "unconnected-(U401-XIN-Pad19)") (class "Default")
      (node (ref "U401") (pin "19") (pinfunction "XIN_19") (pintype "bidirectional"))
    )
  )
)
